# Mobo-v09.net
KiCad netlist of a schematic drawn in EAGLE
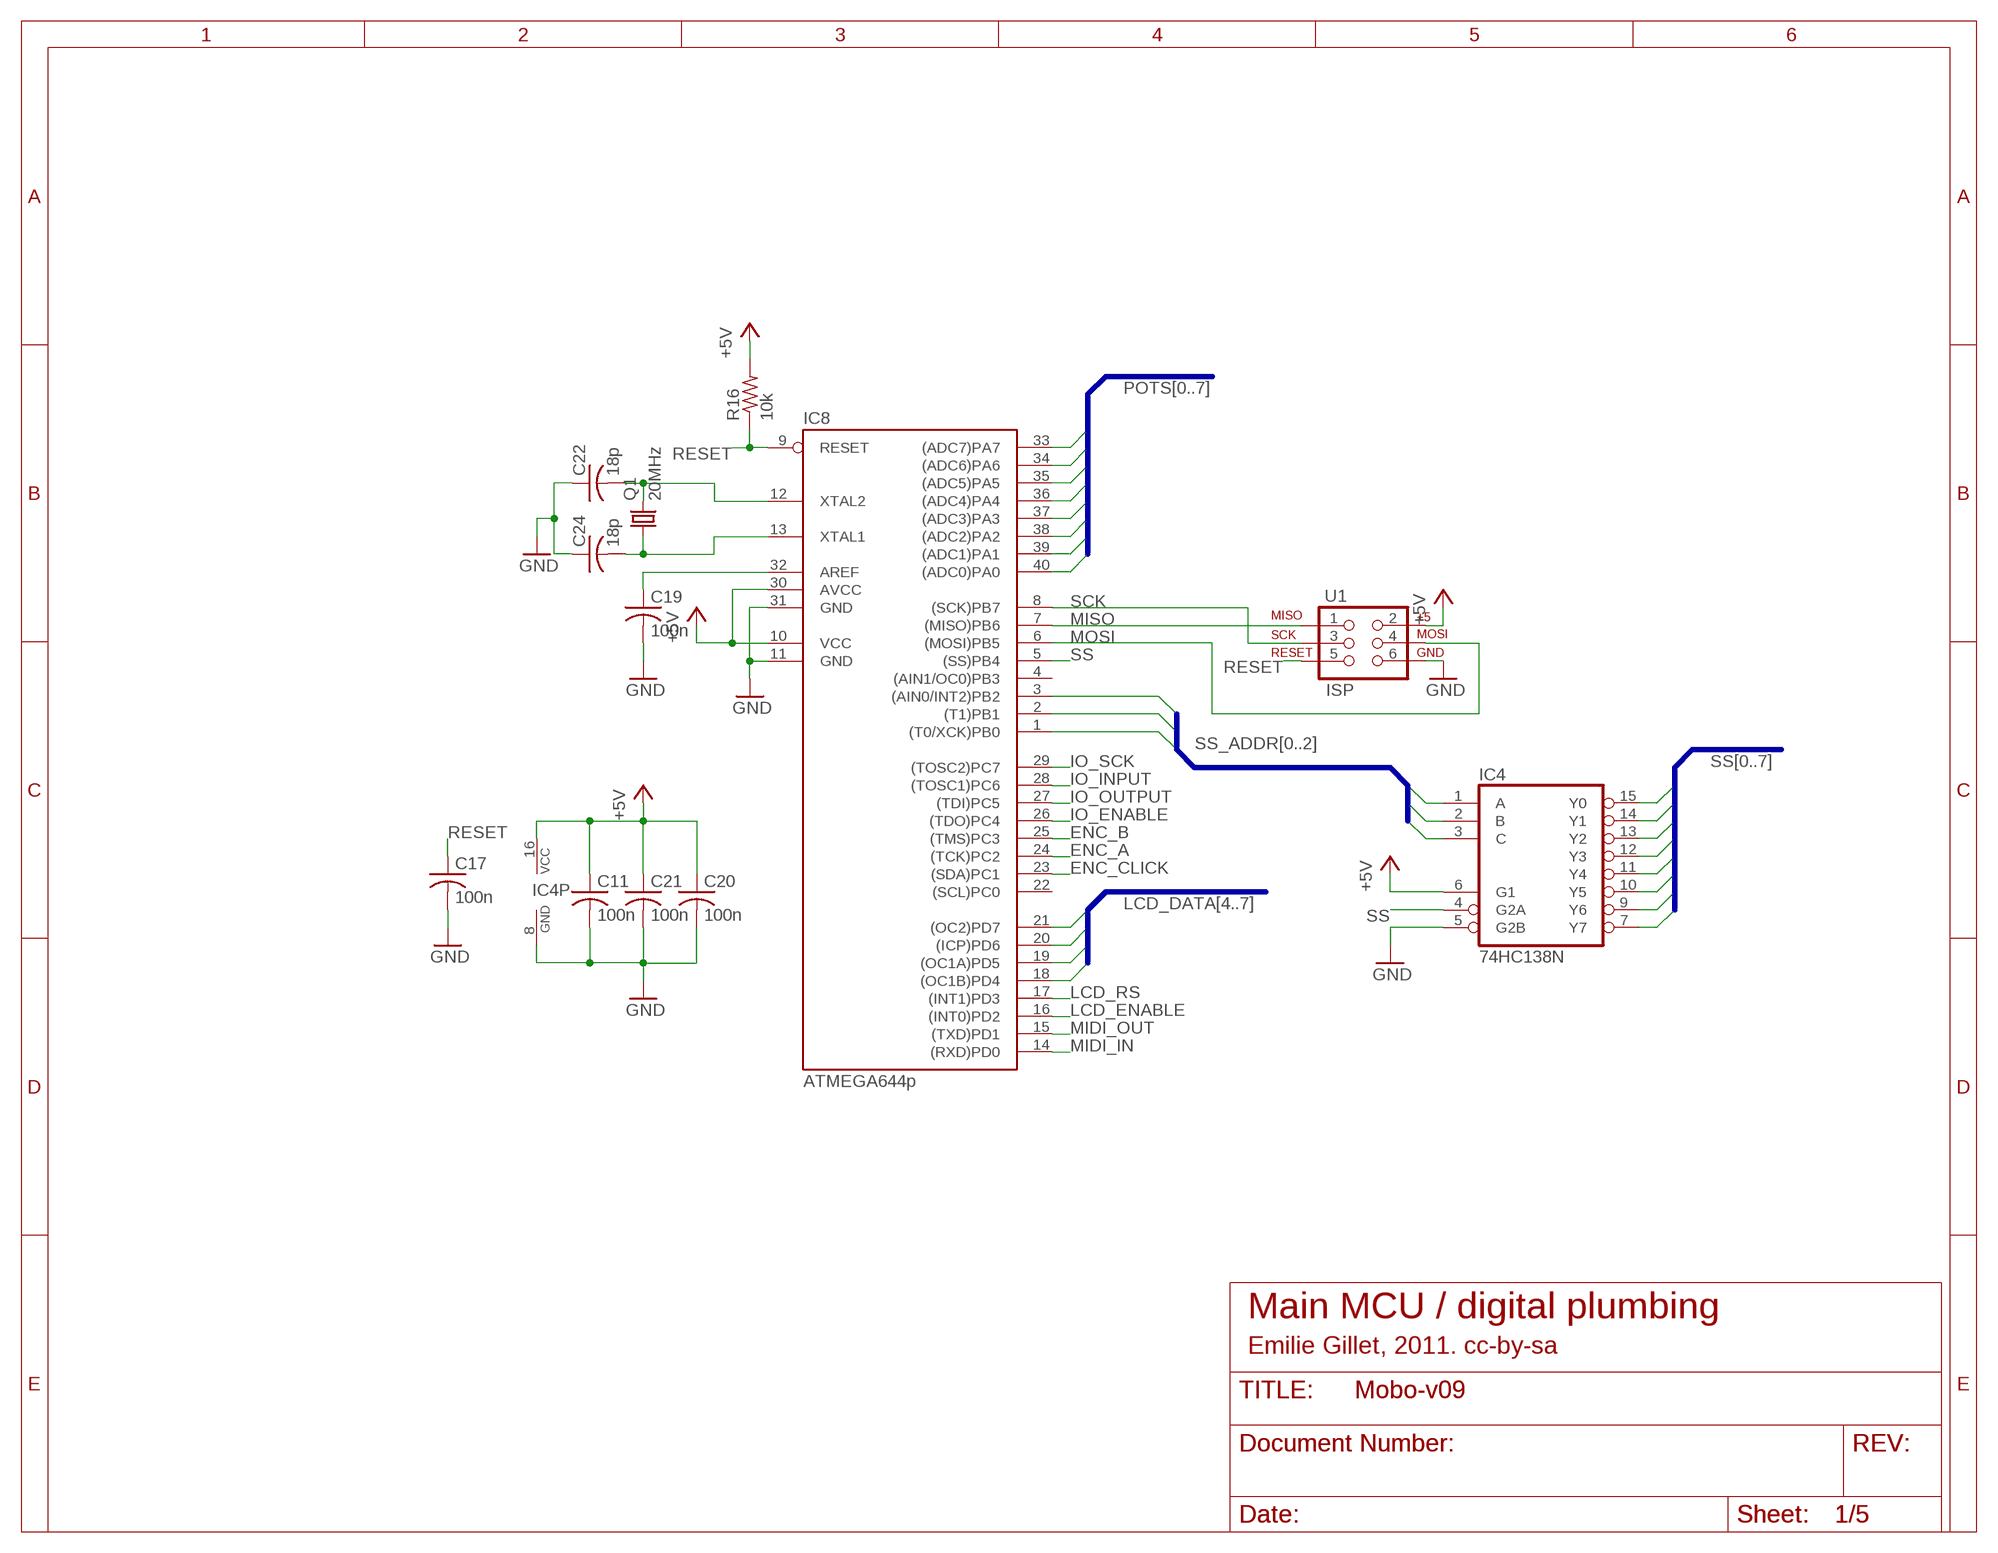
[diagram p0: schematic, sheet 1]
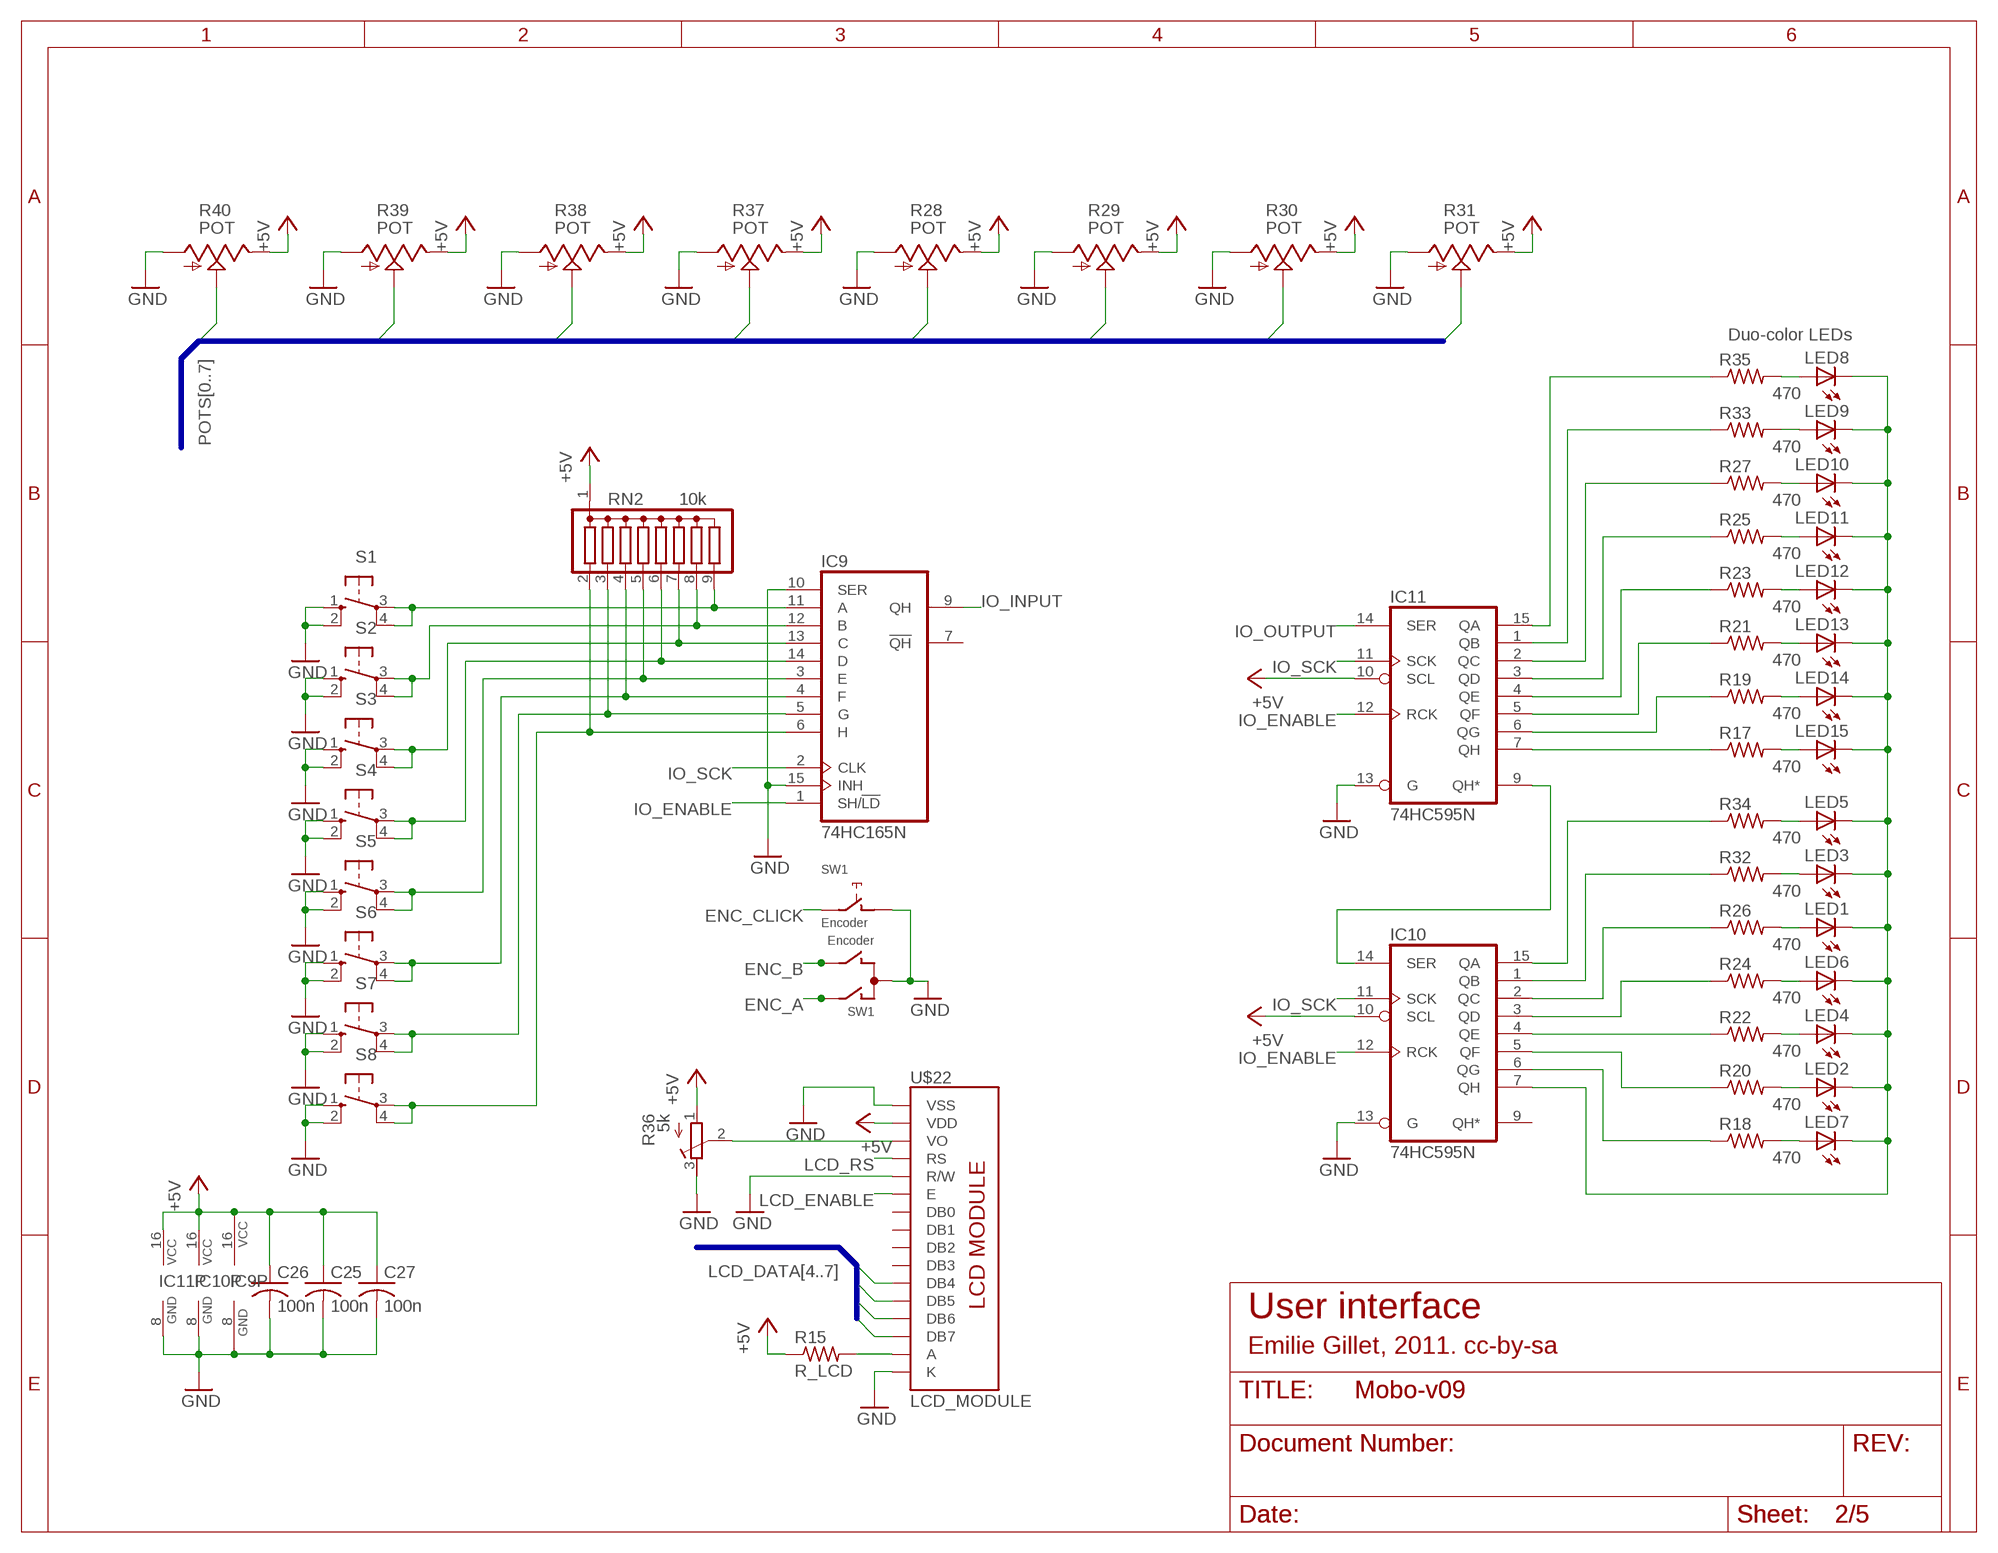
[diagram p1: schematic, sheet 2]
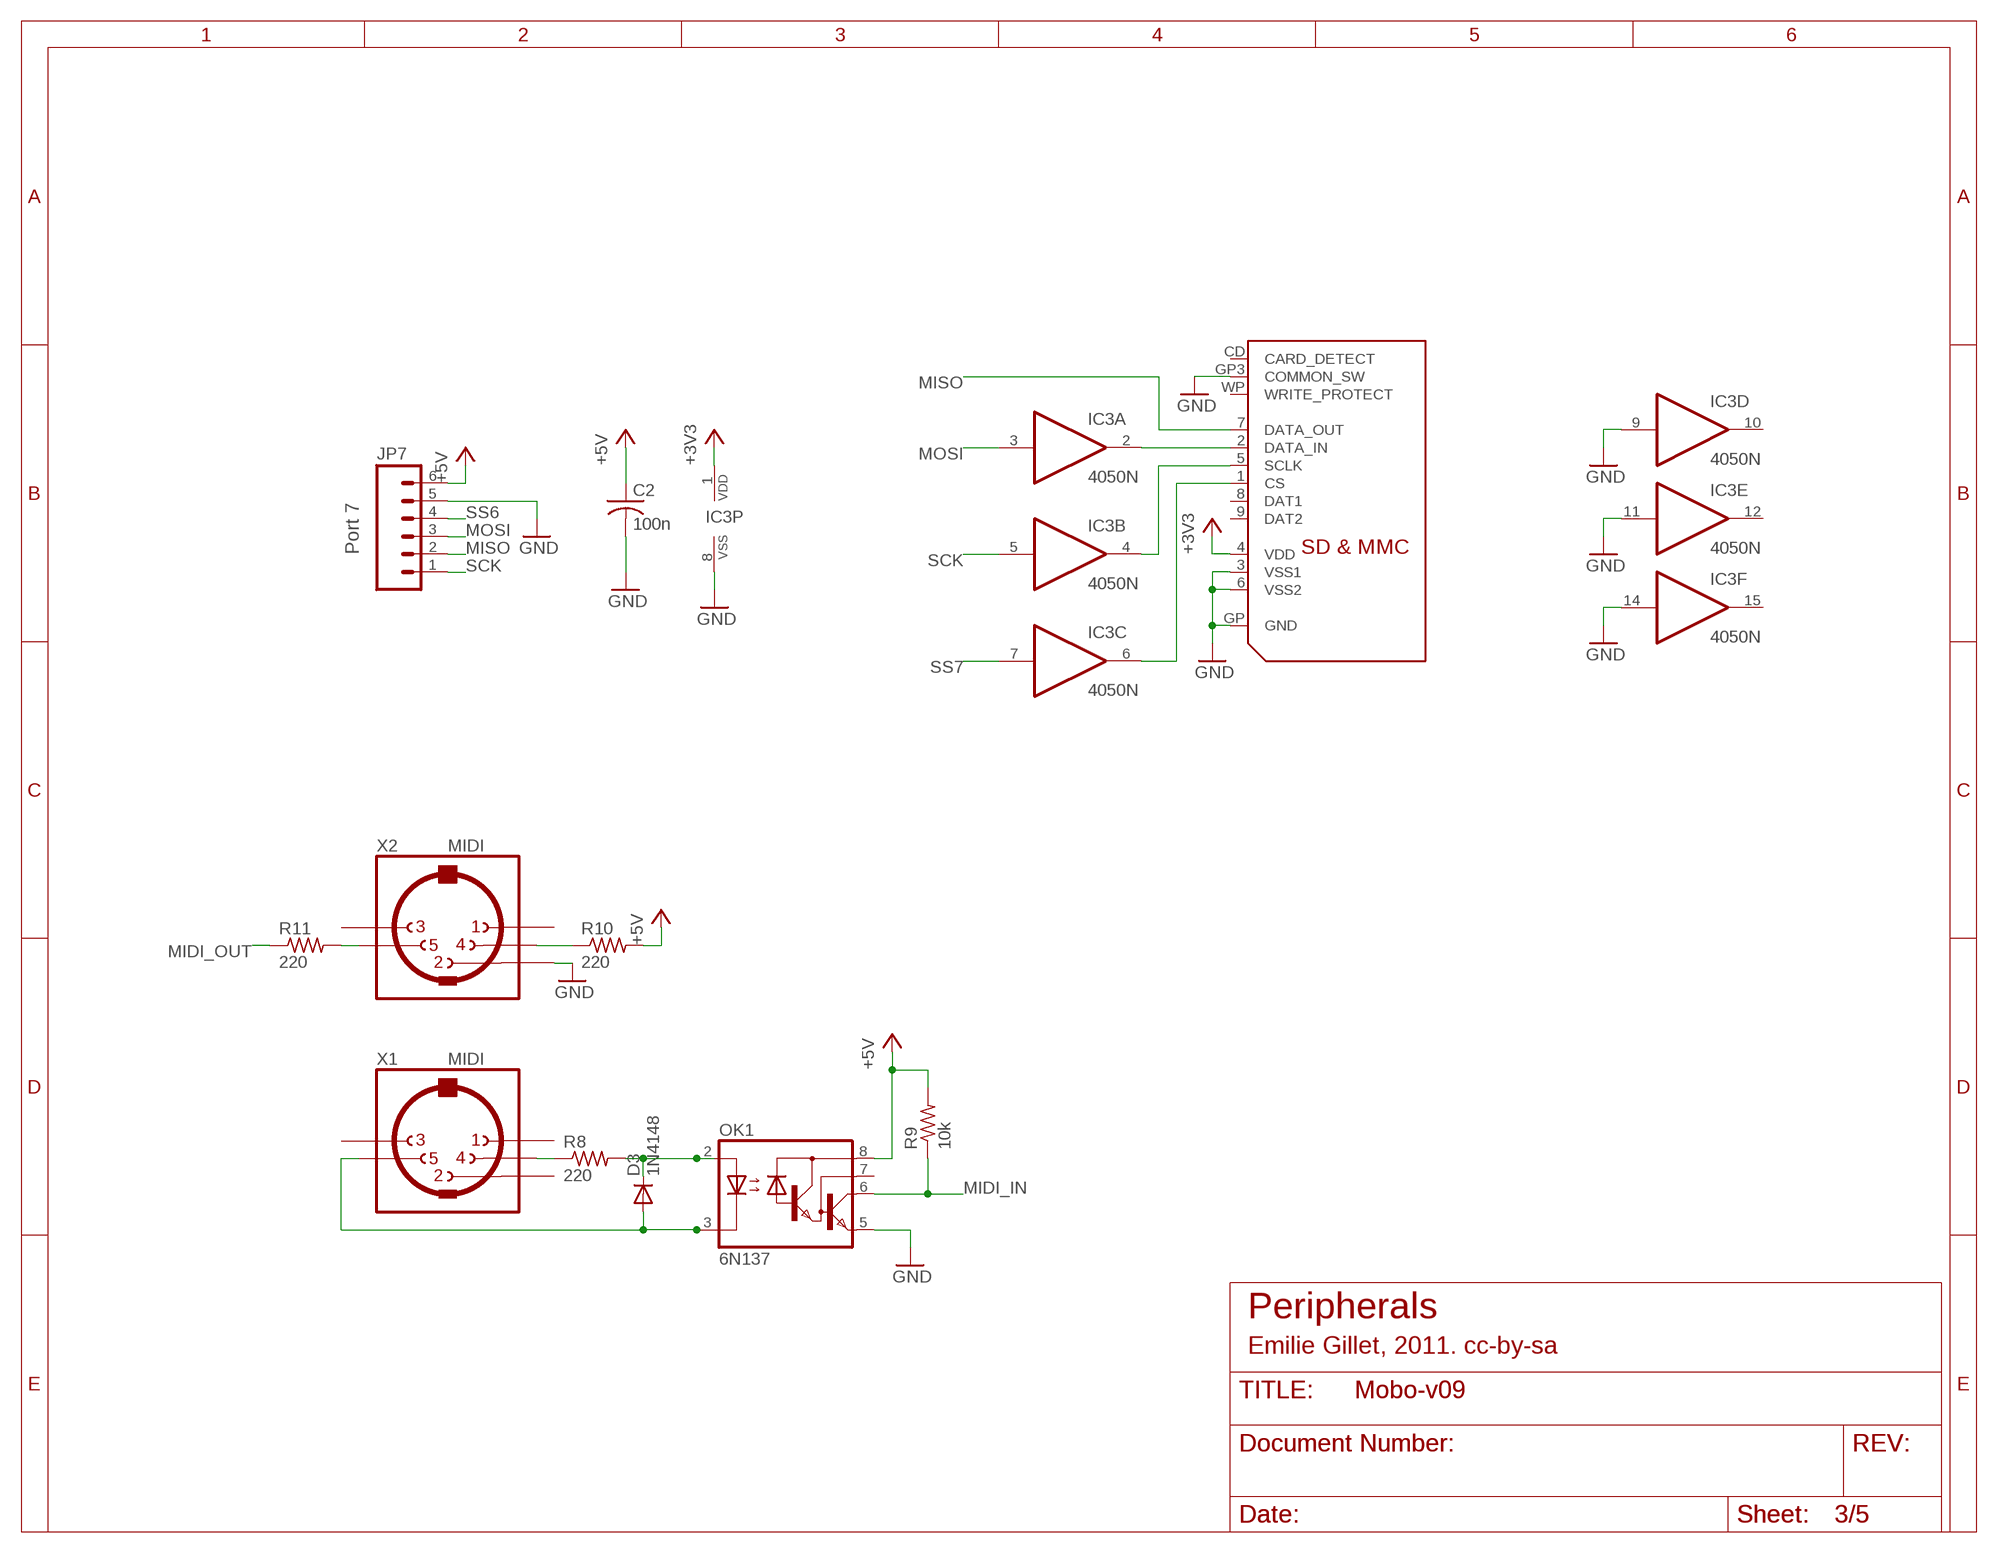
[diagram p2: schematic, sheet 3]
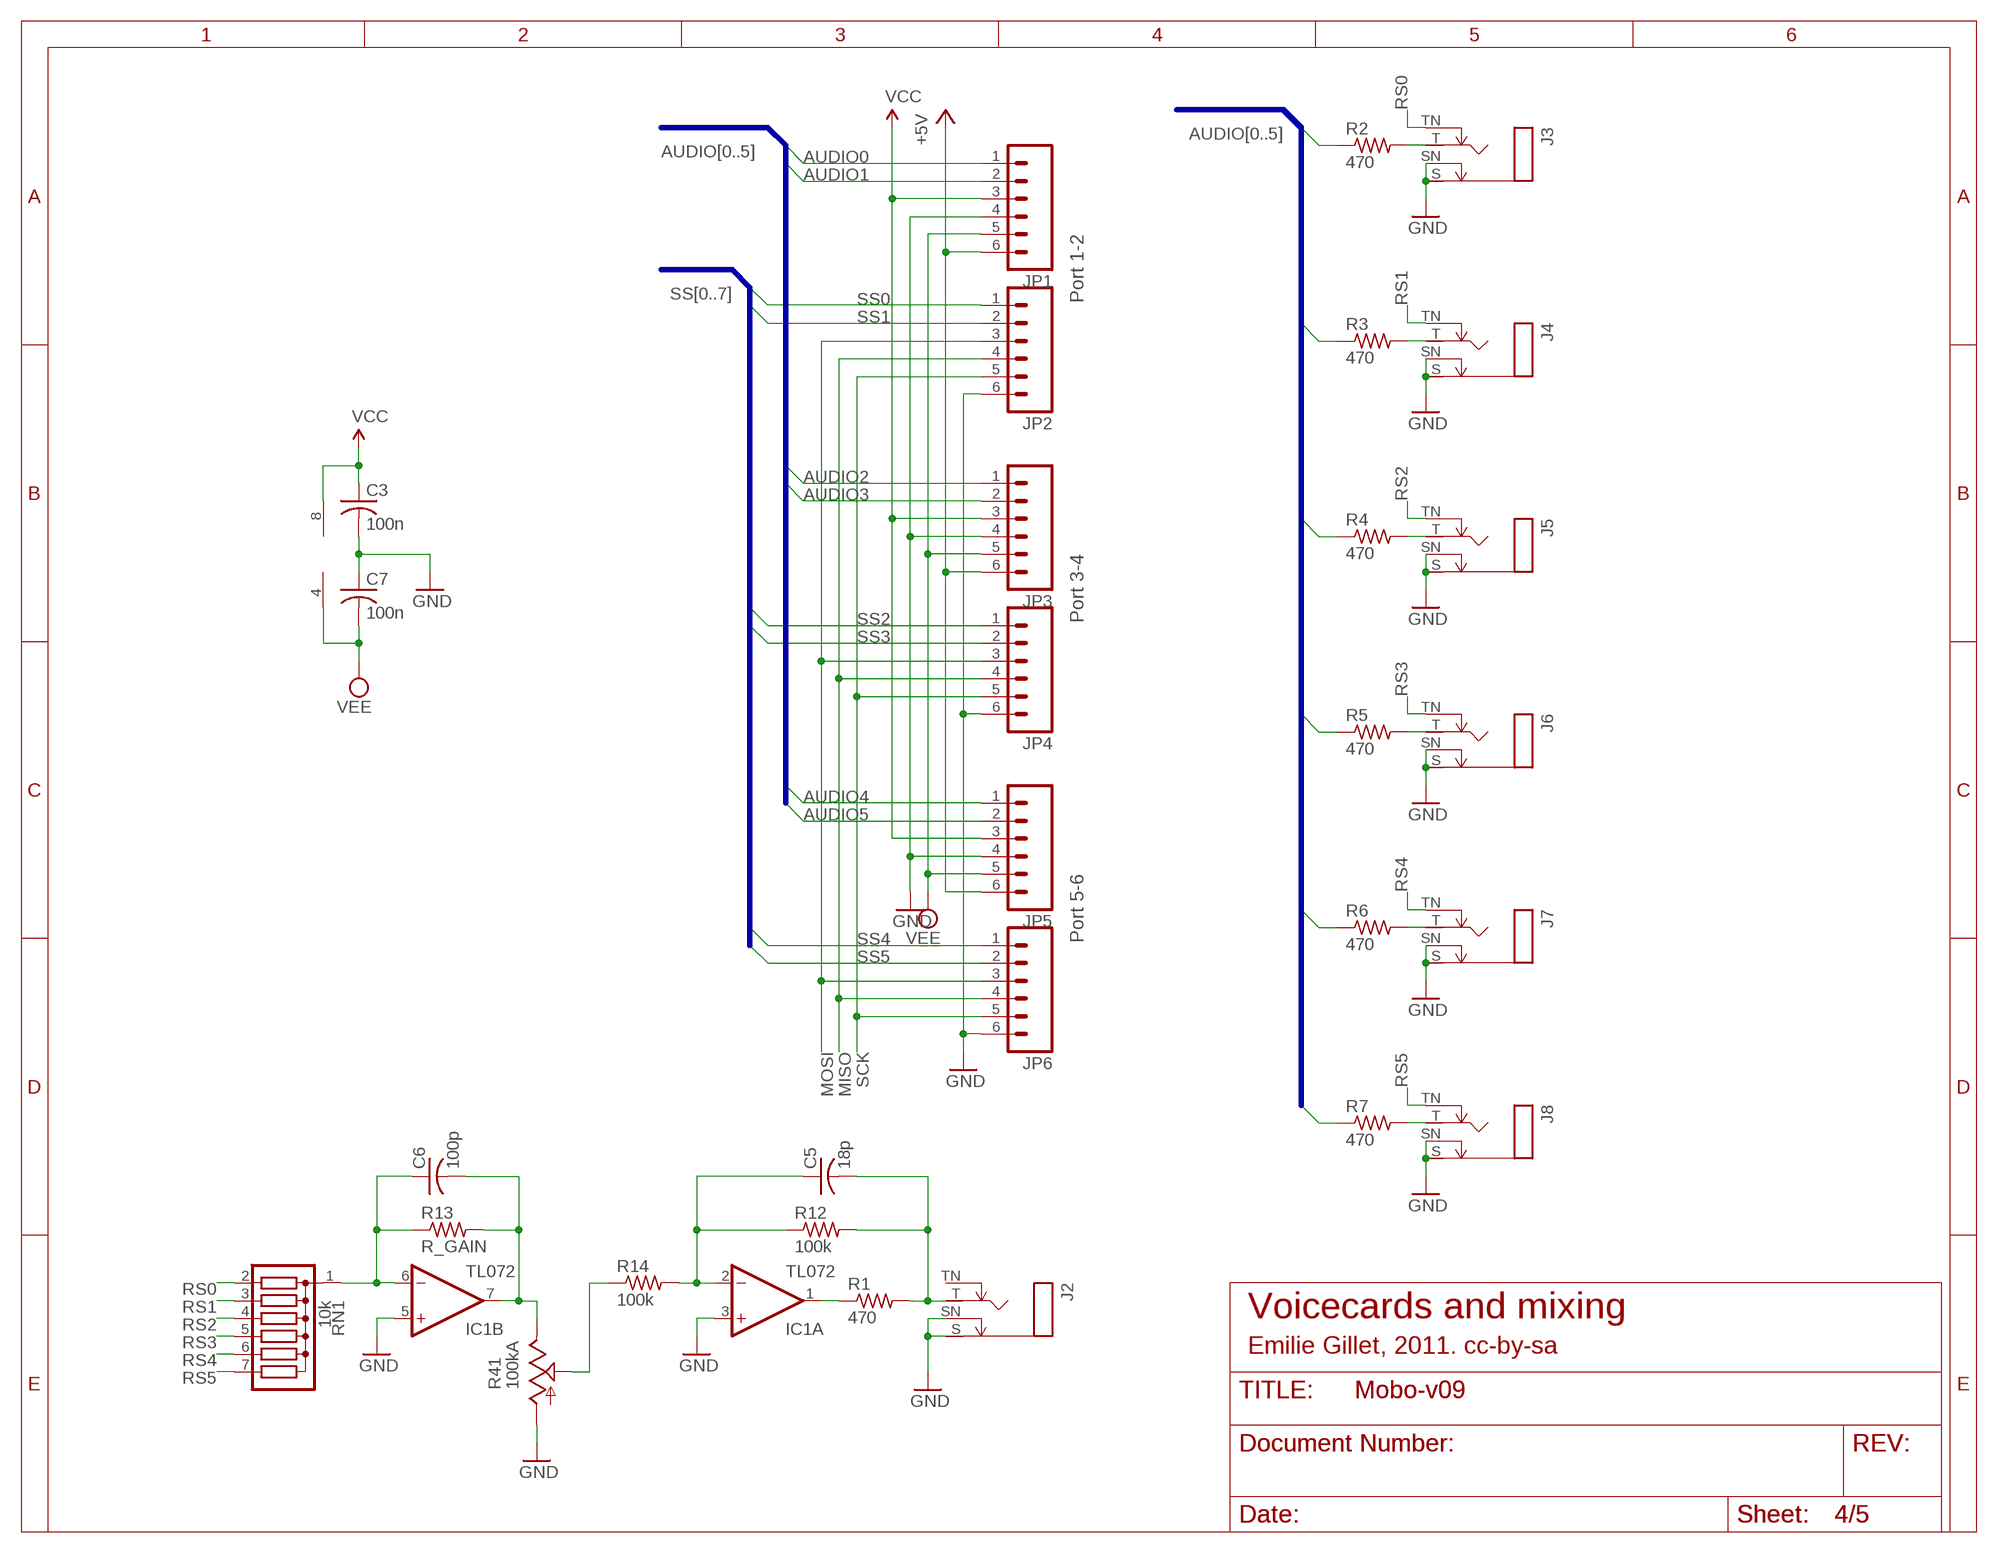
[diagram p3: schematic, sheet 4]
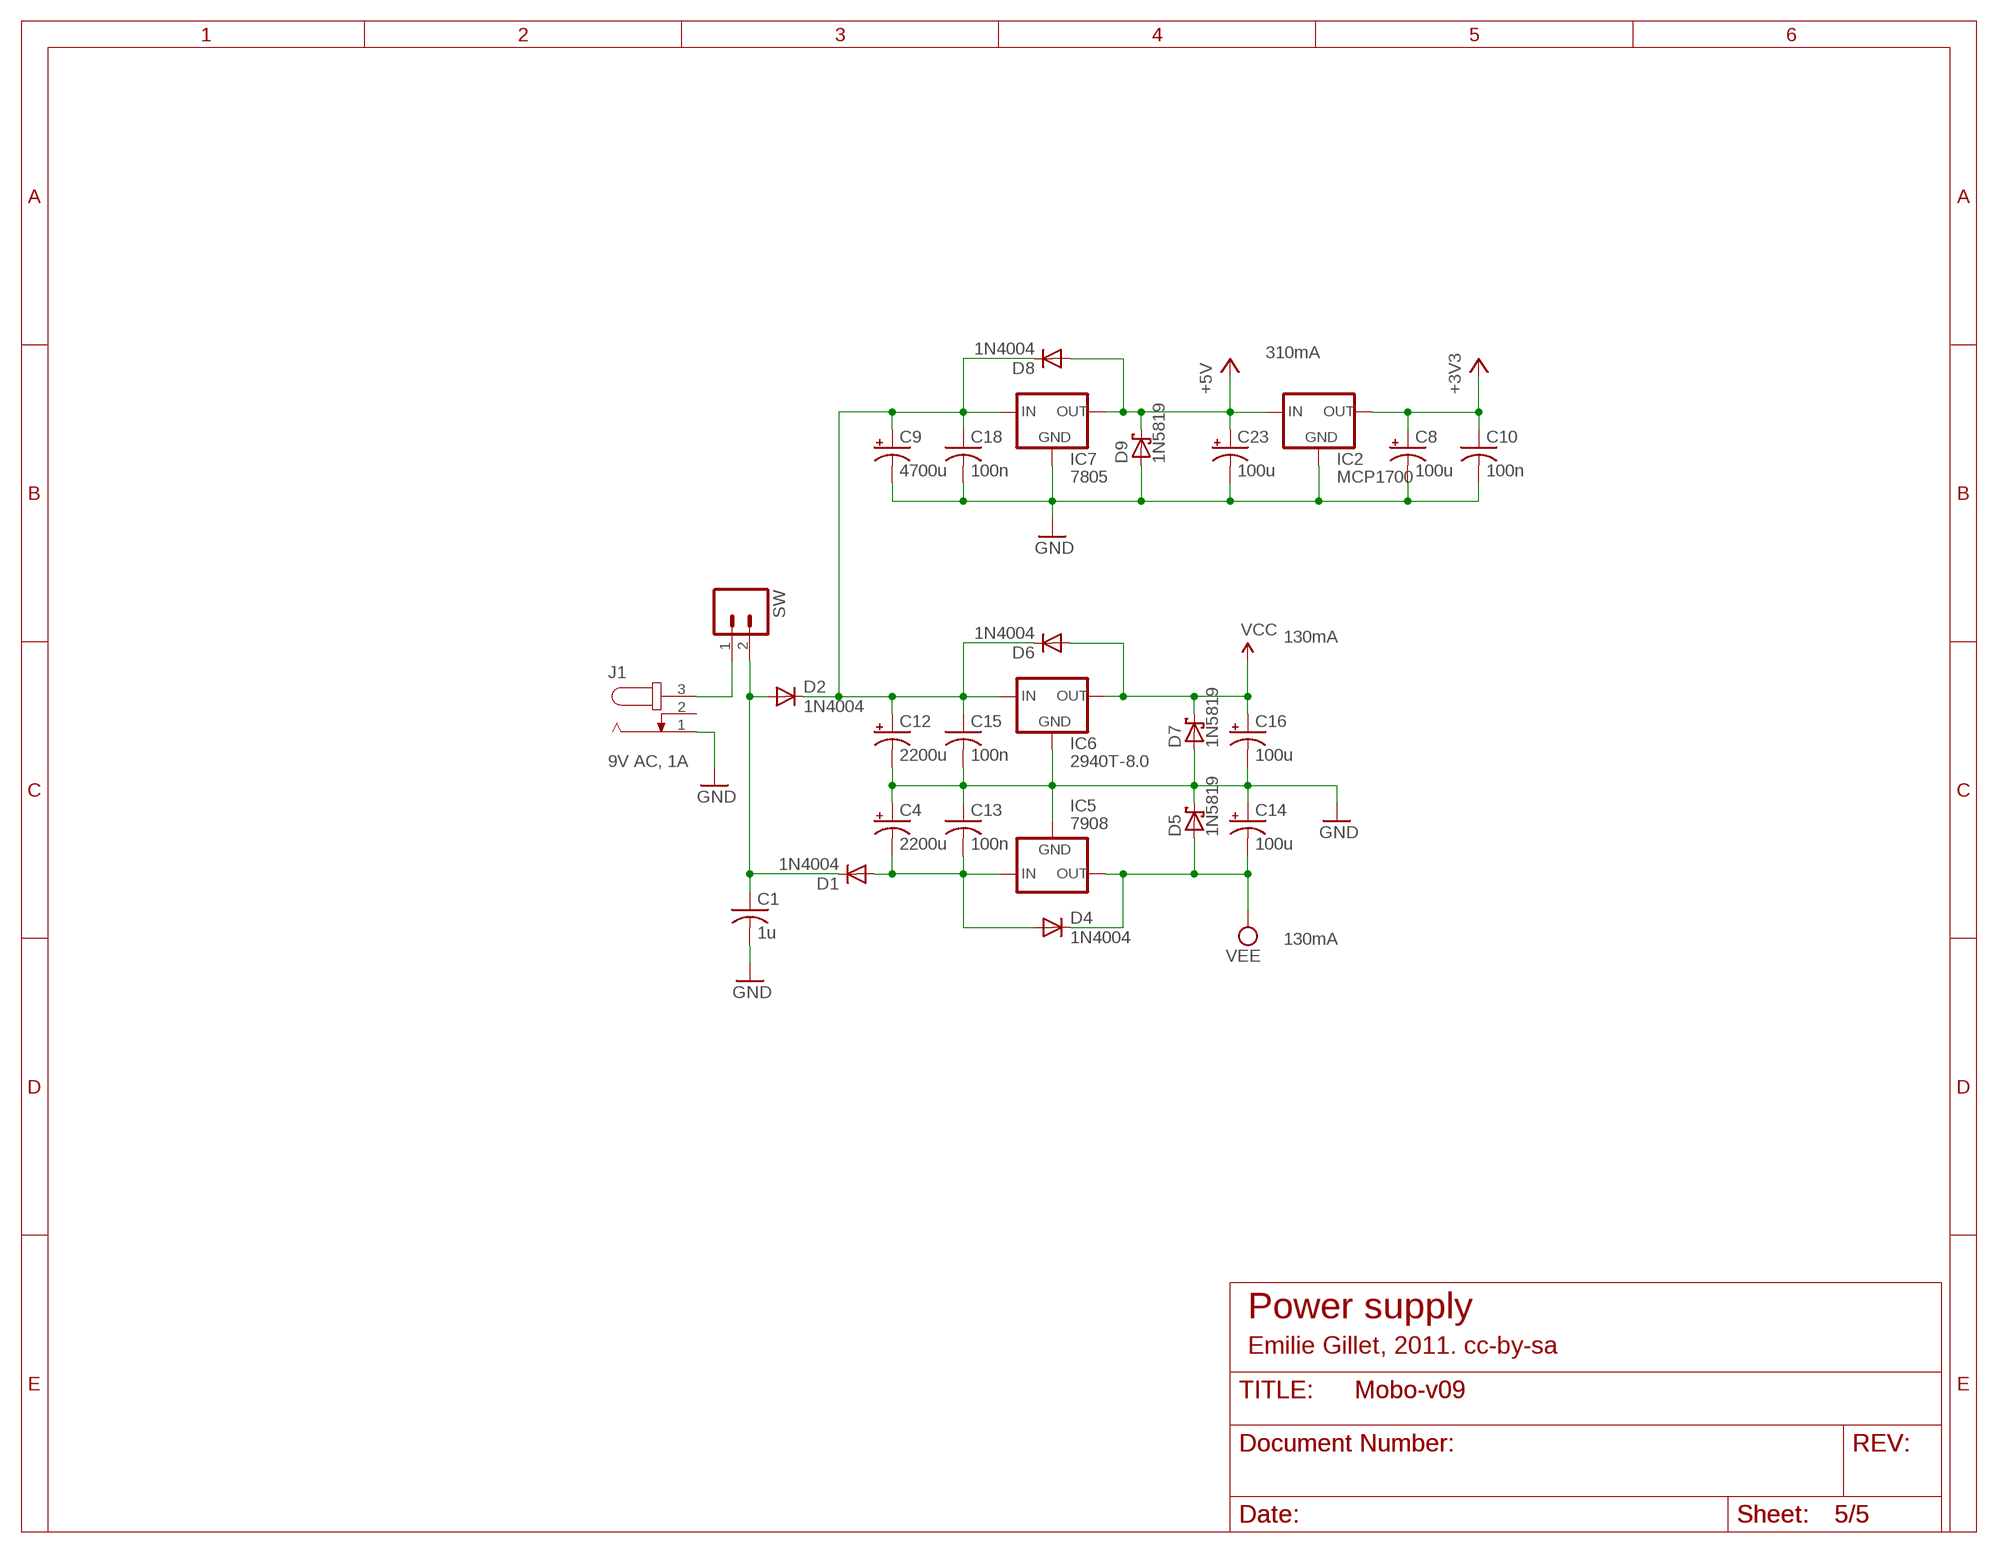
[diagram p4: schematic, sheet 5]

(export (version "E")
  (design (tool "Eeschema 10.0.6"))
  (components
    (comp (ref "C2")
      (value "100n")
      (footprint "eagle-import:C025-024X044")
      (libsource (lib "eagle-import") (part "C-US025-024X044"))
    )
    (comp (ref "D3")
      (value "1N4148")
      (footprint "eagle-import:D-5")
      (libsource (lib "eagle-import") (part "DIODE-D-5"))
    )
    (comp (ref "IC3")
      (value "4050N")
      (footprint "eagle-import:DIL16")
      (libsource (lib "eagle-import") (part "4050N"))
    )
    (comp (ref "JP7")
      (value "M06SIP")
      (footprint "eagle-import:1X06")
      (libsource (lib "eagle-import") (part "M06SIP"))
    )
    (comp (ref "OK1")
      (value "6N137")
      (footprint "eagle-import:DIL08")
      (libsource (lib "eagle-import") (part "6N138"))
    )
    (comp (ref "R8")
      (value "220")
      (footprint "eagle-import:0204_7")
      (libsource (lib "eagle-import") (part "R-US_0204/7"))
    )
    (comp (ref "R9")
      (value "10k")
      (footprint "eagle-import:0204_7")
      (libsource (lib "eagle-import") (part "R-US_0204/7"))
    )
    (comp (ref "R10")
      (value "220")
      (footprint "eagle-import:0204_7")
      (libsource (lib "eagle-import") (part "R-US_0204/7"))
    )
    (comp (ref "R11")
      (value "220")
      (footprint "eagle-import:0204_7")
      (libsource (lib "eagle-import") (part "R-US_0204/7"))
    )
    (comp (ref "U$26")
      (value "SDMMC06132")
      (footprint "eagle-import:06132")
      (libsource (lib "eagle-import") (part "SDMMC06132"))
    )
    (comp (ref "X1")
      (value "MIDI")
      (footprint "eagle-import:MAB5SH")
      (libsource (lib "eagle-import") (part "MAB5SH"))
    )
    (comp (ref "X2")
      (value "MIDI")
      (footprint "eagle-import:MAB5SH")
      (libsource (lib "eagle-import") (part "MAB5SH"))
    )
    (comp (ref "C1")
      (value "1u")
      (footprint "eagle-import:C075-052X106")
      (libsource (lib "eagle-import") (part "C-US075-052X106"))
    )
    (comp (ref "C4")
      (value "2200u")
      (footprint "eagle-import:E5-13")
      (libsource (lib "eagle-import") (part "CPOL-USE5-13"))
    )
    (comp (ref "C8")
      (value "100u")
      (footprint "eagle-import:E2,5-7")
      (libsource (lib "eagle-import") (part "CPOL-USE2.5-7"))
    )
    (comp (ref "C9")
      (value "4700u")
      (footprint "eagle-import:E7,5-16")
      (libsource (lib "eagle-import") (part "CPOL-USE7.5-16"))
    )
    (comp (ref "C10")
      (value "100n")
      (footprint "eagle-import:C025-024X044")
      (libsource (lib "eagle-import") (part "C-US025-024X044"))
    )
    (comp (ref "C12")
      (value "2200u")
      (footprint "eagle-import:E5-13")
      (libsource (lib "eagle-import") (part "CPOL-USE5-13"))
    )
    (comp (ref "C13")
      (value "100n")
      (footprint "eagle-import:C025-025X050")
      (libsource (lib "eagle-import") (part "C-US025-025X050"))
    )
    (comp (ref "C14")
      (value "100u")
      (footprint "eagle-import:E2,5-7")
      (libsource (lib "eagle-import") (part "CPOL-USE2.5-7"))
    )
    (comp (ref "C15")
      (value "100n")
      (footprint "eagle-import:C025-025X050")
      (libsource (lib "eagle-import") (part "C-US025-025X050"))
    )
    (comp (ref "C16")
      (value "100u")
      (footprint "eagle-import:E2,5-7")
      (libsource (lib "eagle-import") (part "CPOL-USE2.5-7"))
    )
    (comp (ref "C18")
      (value "100n")
      (footprint "eagle-import:C025-025X050")
      (libsource (lib "eagle-import") (part "C-US025-025X050"))
    )
    (comp (ref "C23")
      (value "100u")
      (footprint "eagle-import:E2,5-7")
      (libsource (lib "eagle-import") (part "CPOL-USE2.5-7"))
    )
    (comp (ref "D1")
      (value "1N4004")
      (footprint "eagle-import:DO41-10")
      (libsource (lib "eagle-import") (part "1N4004"))
    )
    (comp (ref "D2")
      (value "1N4004")
      (footprint "eagle-import:DO41-10")
      (libsource (lib "eagle-import") (part "1N4004"))
    )
    (comp (ref "D4")
      (value "1N4004")
      (footprint "eagle-import:DO41-10")
      (libsource (lib "eagle-import") (part "1N4004"))
    )
    (comp (ref "D5")
      (value "1N5819")
      (footprint "eagle-import:DO41-7.6")
      (libsource (lib "eagle-import") (part "1N5819-T"))
    )
    (comp (ref "D6")
      (value "1N4004")
      (footprint "eagle-import:DO41-10")
      (libsource (lib "eagle-import") (part "1N4004"))
    )
    (comp (ref "D7")
      (value "1N5819")
      (footprint "eagle-import:DO41-7.6")
      (libsource (lib "eagle-import") (part "1N5819-T"))
    )
    (comp (ref "D8")
      (value "1N4004")
      (footprint "eagle-import:DO41-10")
      (libsource (lib "eagle-import") (part "1N4004"))
    )
    (comp (ref "D9")
      (value "1N5819")
      (footprint "eagle-import:DO41-7.6")
      (libsource (lib "eagle-import") (part "1N5819-T"))
    )
    (comp (ref "IC2")
      (value "MCP1700")
      (footprint "eagle-import:TO92-INLINE")
      (libsource (lib "eagle-import") (part "MCP1700INLINE"))
    )
    (comp (ref "IC5")
      (value "7908")
      (footprint "eagle-import:79XXL")
      (libsource (lib "eagle-import") (part "79XXL"))
    )
    (comp (ref "IC6")
      (value "2940T-8.0")
      (footprint "eagle-import:78XXL")
      (libsource (lib "eagle-import") (part "78XXL"))
    )
    (comp (ref "IC7")
      (value "7805")
      (footprint "eagle-import:78XXL")
      (libsource (lib "eagle-import") (part "v-reg_409_78XXL"))
    )
    (comp (ref "J1")
      (value "JACK-PLUG2")
      (footprint "eagle-import:SPC4078_BIG_HOLES")
      (libsource (lib "eagle-import") (part "JACK-PLUG2"))
    )
    (comp (ref "SW")
      (value "M02PTH")
      (footprint "eagle-import:1X02")
      (libsource (lib "eagle-import") (part "M02PTH"))
    )
    (comp (ref "C3")
      (value "100n")
      (footprint "eagle-import:C025-024X044")
      (libsource (lib "eagle-import") (part "C-US025-024X044"))
    )
    (comp (ref "C5")
      (value "18p")
      (footprint "eagle-import:C025-024X044")
      (libsource (lib "eagle-import") (part "C-US025-024X044"))
    )
    (comp (ref "C6")
      (value "100p")
      (footprint "eagle-import:C025-024X044")
      (libsource (lib "eagle-import") (part "C-US025-024X044"))
    )
    (comp (ref "C7")
      (value "100n")
      (footprint "eagle-import:C025-024X044")
      (libsource (lib "eagle-import") (part "C-US025-024X044"))
    )
    (comp (ref "IC1")
      (value "TL072")
      (footprint "eagle-import:DIL08")
      (libsource (lib "eagle-import") (part "TL072P"))
    )
    (comp (ref "J2")
      (value "MONOSWSLIM")
      (footprint "eagle-import:NRJ4HF")
      (libsource (lib "eagle-import") (part "MONOSWSLIM"))
    )
    (comp (ref "J3")
      (value "MONOSWSLIM")
      (footprint "eagle-import:NRJ4HF")
      (libsource (lib "eagle-import") (part "MONOSWSLIM"))
    )
    (comp (ref "J4")
      (value "MONOSWSLIM")
      (footprint "eagle-import:NRJ4HF")
      (libsource (lib "eagle-import") (part "MONOSWSLIM"))
    )
    (comp (ref "J5")
      (value "MONOSWSLIM")
      (footprint "eagle-import:NRJ4HF")
      (libsource (lib "eagle-import") (part "MONOSWSLIM"))
    )
    (comp (ref "J6")
      (value "MONOSWSLIM")
      (footprint "eagle-import:NRJ4HF")
      (libsource (lib "eagle-import") (part "MONOSWSLIM"))
    )
    (comp (ref "J7")
      (value "MONOSWSLIM")
      (footprint "eagle-import:NRJ4HF")
      (libsource (lib "eagle-import") (part "MONOSWSLIM"))
    )
    (comp (ref "J8")
      (value "MONOSWSLIM")
      (footprint "eagle-import:NRJ4HF")
      (libsource (lib "eagle-import") (part "MONOSWSLIM"))
    )
    (comp (ref "JP1")
      (value "M06SIP")
      (footprint "eagle-import:1X06")
      (libsource (lib "eagle-import") (part "M06SIP"))
    )
    (comp (ref "JP2")
      (value "M06SIP")
      (footprint "eagle-import:1X06")
      (libsource (lib "eagle-import") (part "M06SIP"))
    )
    (comp (ref "JP3")
      (value "M06SIP")
      (footprint "eagle-import:1X06")
      (libsource (lib "eagle-import") (part "M06SIP"))
    )
    (comp (ref "JP4")
      (value "M06SIP")
      (footprint "eagle-import:1X06")
      (libsource (lib "eagle-import") (part "M06SIP"))
    )
    (comp (ref "JP5")
      (value "M06SIP")
      (footprint "eagle-import:1X06")
      (libsource (lib "eagle-import") (part "M06SIP"))
    )
    (comp (ref "JP6")
      (value "M06SIP")
      (footprint "eagle-import:1X06")
      (libsource (lib "eagle-import") (part "M06SIP"))
    )
    (comp (ref "R1")
      (value "470")
      (footprint "eagle-import:0204_7")
      (libsource (lib "eagle-import") (part "R-US_0204/7"))
    )
    (comp (ref "R2")
      (value "470")
      (footprint "eagle-import:0204_7")
      (libsource (lib "eagle-import") (part "R-US_0204/7"))
    )
    (comp (ref "R3")
      (value "470")
      (footprint "eagle-import:0204_7")
      (libsource (lib "eagle-import") (part "R-US_0204/7"))
    )
    (comp (ref "R4")
      (value "470")
      (footprint "eagle-import:0204_7")
      (libsource (lib "eagle-import") (part "R-US_0204/7"))
    )
    (comp (ref "R5")
      (value "470")
      (footprint "eagle-import:0204_7")
      (libsource (lib "eagle-import") (part "R-US_0204/7"))
    )
    (comp (ref "R6")
      (value "470")
      (footprint "eagle-import:0204_7")
      (libsource (lib "eagle-import") (part "R-US_0204/7"))
    )
    (comp (ref "R7")
      (value "470")
      (footprint "eagle-import:0204_7")
      (libsource (lib "eagle-import") (part "R-US_0204/7"))
    )
    (comp (ref "R12")
      (value "100k")
      (footprint "eagle-import:0204_7")
      (libsource (lib "eagle-import") (part "R-US_0204/7"))
    )
    (comp (ref "R13")
      (value "R_GAIN")
      (footprint "eagle-import:0204_7")
      (libsource (lib "eagle-import") (part "R-US_0204/7"))
    )
    (comp (ref "R14")
      (value "100k")
      (footprint "eagle-import:0204_7")
      (libsource (lib "eagle-import") (part "R-US_0204/7"))
    )
    (comp (ref "R41")
      (value "100kA")
      (footprint "eagle-import:ALPS_POT_VERTICAL")
      (libsource (lib "eagle-import") (part "POT_USVERTICAL"))
    )
    (comp (ref "RN1")
      (value "10k")
      (footprint "eagle-import:SIL7")
      (libsource (lib "eagle-import") (part "G06R"))
    )
    (comp (ref "C11")
      (value "100n")
      (footprint "eagle-import:C025-024X044")
      (libsource (lib "eagle-import") (part "C-US025-024X044"))
    )
    (comp (ref "C17")
      (value "100n")
      (footprint "eagle-import:C025-024X044")
      (libsource (lib "eagle-import") (part "C-US025-024X044"))
    )
    (comp (ref "C19")
      (value "100n")
      (footprint "eagle-import:C025-024X044")
      (libsource (lib "eagle-import") (part "C-US025-024X044"))
    )
    (comp (ref "C20")
      (value "100n")
      (footprint "eagle-import:C025-024X044")
      (libsource (lib "eagle-import") (part "C-US025-024X044"))
    )
    (comp (ref "C21")
      (value "100n")
      (footprint "eagle-import:C025-024X044")
      (libsource (lib "eagle-import") (part "C-US025-024X044"))
    )
    (comp (ref "C22")
      (value "18p")
      (footprint "eagle-import:C025-024X044")
      (libsource (lib "eagle-import") (part "C-US025-024X044"))
    )
    (comp (ref "C24")
      (value "18p")
      (footprint "eagle-import:C025-024X044")
      (libsource (lib "eagle-import") (part "C-US025-024X044"))
    )
    (comp (ref "IC4")
      (value "74HC138N")
      (footprint "eagle-import:DIL16")
      (libsource (lib "eagle-import") (part "74138NHC"))
    )
    (comp (ref "IC8")
      (value "ATMEGA644p")
      (footprint "eagle-import:DIL40")
      (libsource (lib "eagle-import") (part "MEGA16-P"))
    )
    (comp (ref "Q1")
      (value "20MHz")
      (footprint "eagle-import:HC49U-V")
      (libsource (lib "eagle-import") (part "CRYSTALHC49U-V"))
    )
    (comp (ref "R16")
      (value "10k")
      (footprint "eagle-import:0204_7")
      (libsource (lib "eagle-import") (part "R-US_0204/7"))
    )
    (comp (ref "U1")
      (value "ISP")
      (footprint "eagle-import:2X3")
      (libsource (lib "eagle-import") (part "AVR_SPI_PRG_6PTH"))
    )
    (comp (ref "C25")
      (value "100n")
      (footprint "eagle-import:C025-024X044")
      (libsource (lib "eagle-import") (part "C-US025-024X044"))
    )
    (comp (ref "C26")
      (value "100n")
      (footprint "eagle-import:C025-024X044")
      (libsource (lib "eagle-import") (part "C-US025-024X044"))
    )
    (comp (ref "C27")
      (value "100n")
      (footprint "eagle-import:C025-024X044")
      (libsource (lib "eagle-import") (part "C-US025-024X044"))
    )
    (comp (ref "IC9")
      (value "74HC165N")
      (footprint "eagle-import:DIL16")
      (libsource (lib "eagle-import") (part "74165NLS"))
    )
    (comp (ref "IC10")
      (value "74HC595N")
      (footprint "eagle-import:DIL16")
      (libsource (lib "eagle-import") (part "74595NHC"))
    )
    (comp (ref "IC11")
      (value "74HC595N")
      (footprint "eagle-import:DIL16")
      (libsource (lib "eagle-import") (part "74595NHC"))
    )
    (comp (ref "LED1")
      (value "LED3MM")
      (footprint "eagle-import:LED3MM")
      (libsource (lib "eagle-import") (part "LED3MM"))
    )
    (comp (ref "LED2")
      (value "LED3MM")
      (footprint "eagle-import:LED3MM")
      (libsource (lib "eagle-import") (part "LED3MM"))
    )
    (comp (ref "LED3")
      (value "LED3MM")
      (footprint "eagle-import:LED3MM")
      (libsource (lib "eagle-import") (part "LED3MM"))
    )
    (comp (ref "LED4")
      (value "LED3MM")
      (footprint "eagle-import:LED3MM")
      (libsource (lib "eagle-import") (part "LED3MM"))
    )
    (comp (ref "LED5")
      (value "LED3MM")
      (footprint "eagle-import:LED3MM")
      (libsource (lib "eagle-import") (part "LED3MM"))
    )
    (comp (ref "LED6")
      (value "LED3MM")
      (footprint "eagle-import:LED3MM")
      (libsource (lib "eagle-import") (part "LED3MM"))
    )
    (comp (ref "LED7")
      (value "LED3MM")
      (footprint "eagle-import:LED3MM")
      (libsource (lib "eagle-import") (part "LED3MM"))
    )
    (comp (ref "LED8")
      (value "LED3MM")
      (footprint "eagle-import:LED3MM")
      (libsource (lib "eagle-import") (part "LED3MM"))
    )
    (comp (ref "LED9")
      (value "LED3MM")
      (footprint "eagle-import:LED3MM")
      (libsource (lib "eagle-import") (part "LED3MM"))
    )
    (comp (ref "LED10")
      (value "LED3MM")
      (footprint "eagle-import:LED3MM")
      (libsource (lib "eagle-import") (part "LED3MM"))
    )
    (comp (ref "LED11")
      (value "LED3MM")
      (footprint "eagle-import:LED3MM")
      (libsource (lib "eagle-import") (part "LED3MM"))
    )
    (comp (ref "LED12")
      (value "LED3MM")
      (footprint "eagle-import:LED3MM")
      (libsource (lib "eagle-import") (part "LED3MM"))
    )
    (comp (ref "LED13")
      (value "LED3MM")
      (footprint "eagle-import:LED3MM")
      (libsource (lib "eagle-import") (part "LED3MM"))
    )
    (comp (ref "LED14")
      (value "LED3MM")
      (footprint "eagle-import:LED3MM")
      (libsource (lib "eagle-import") (part "LED3MM"))
    )
    (comp (ref "LED15")
      (value "LED3MM")
      (footprint "eagle-import:LED3MM")
      (libsource (lib "eagle-import") (part "LED3MM"))
    )
    (comp (ref "R15")
      (value "R_LCD")
      (footprint "eagle-import:0204_7")
      (libsource (lib "eagle-import") (part "R-US_0204/7"))
    )
    (comp (ref "R17")
      (value "470")
      (footprint "eagle-import:0204_7")
      (libsource (lib "eagle-import") (part "R-US_0204/7"))
    )
    (comp (ref "R18")
      (value "470")
      (footprint "eagle-import:0204_7")
      (libsource (lib "eagle-import") (part "R-US_0204/7"))
    )
    (comp (ref "R19")
      (value "470")
      (footprint "eagle-import:0204_7")
      (libsource (lib "eagle-import") (part "R-US_0204/7"))
    )
    (comp (ref "R20")
      (value "470")
      (footprint "eagle-import:0204_7")
      (libsource (lib "eagle-import") (part "R-US_0204/7"))
    )
    (comp (ref "R21")
      (value "470")
      (footprint "eagle-import:0204_7")
      (libsource (lib "eagle-import") (part "R-US_0204/7"))
    )
    (comp (ref "R22")
      (value "470")
      (footprint "eagle-import:0204_7")
      (libsource (lib "eagle-import") (part "R-US_0204/7"))
    )
    (comp (ref "R23")
      (value "470")
      (footprint "eagle-import:0204_7")
      (libsource (lib "eagle-import") (part "R-US_0204/7"))
    )
    (comp (ref "R24")
      (value "470")
      (footprint "eagle-import:0204_7")
      (libsource (lib "eagle-import") (part "R-US_0204/7"))
    )
    (comp (ref "R25")
      (value "470")
      (footprint "eagle-import:0204_7")
      (libsource (lib "eagle-import") (part "R-US_0204/7"))
    )
    (comp (ref "R26")
      (value "470")
      (footprint "eagle-import:0204_7")
      (libsource (lib "eagle-import") (part "R-US_0204/7"))
    )
    (comp (ref "R27")
      (value "470")
      (footprint "eagle-import:0204_7")
      (libsource (lib "eagle-import") (part "R-US_0204/7"))
    )
    (comp (ref "R28")
      (value "POT")
      (footprint "eagle-import:ALPS_POT_VERTICAL")
      (libsource (lib "eagle-import") (part "POT_USVERTICAL"))
    )
    (comp (ref "R29")
      (value "POT")
      (footprint "eagle-import:ALPS_POT_VERTICAL")
      (libsource (lib "eagle-import") (part "POT_USVERTICAL"))
    )
    (comp (ref "R30")
      (value "POT")
      (footprint "eagle-import:ALPS_POT_VERTICAL")
      (libsource (lib "eagle-import") (part "POT_USVERTICAL"))
    )
    (comp (ref "R31")
      (value "POT")
      (footprint "eagle-import:ALPS_POT_VERTICAL")
      (libsource (lib "eagle-import") (part "POT_USVERTICAL"))
    )
    (comp (ref "R32")
      (value "470")
      (footprint "eagle-import:0204_7")
      (libsource (lib "eagle-import") (part "R-US_0204/7"))
    )
    (comp (ref "R33")
      (value "470")
      (footprint "eagle-import:0204_7")
      (libsource (lib "eagle-import") (part "R-US_0204/7"))
    )
    (comp (ref "R34")
      (value "470")
      (footprint "eagle-import:0204_7")
      (libsource (lib "eagle-import") (part "R-US_0204/7"))
    )
    (comp (ref "R35")
      (value "470")
      (footprint "eagle-import:0204_7")
      (libsource (lib "eagle-import") (part "R-US_0204/7"))
    )
    (comp (ref "R36")
      (value "5k")
      (footprint "eagle-import:RTRIM3339P")
      (libsource (lib "eagle-import") (part "R-TRIMM3339P"))
    )
    (comp (ref "R37")
      (value "POT")
      (footprint "eagle-import:ALPS_POT_VERTICAL")
      (libsource (lib "eagle-import") (part "POT_USVERTICAL"))
    )
    (comp (ref "R38")
      (value "POT")
      (footprint "eagle-import:ALPS_POT_VERTICAL")
      (libsource (lib "eagle-import") (part "POT_USVERTICAL"))
    )
    (comp (ref "R39")
      (value "POT")
      (footprint "eagle-import:ALPS_POT_VERTICAL")
      (libsource (lib "eagle-import") (part "POT_USVERTICAL"))
    )
    (comp (ref "R40")
      (value "POT")
      (footprint "eagle-import:ALPS_POT_VERTICAL")
      (libsource (lib "eagle-import") (part "POT_USVERTICAL"))
    )
    (comp (ref "RN2")
      (value "10k")
      (footprint "eagle-import:SIL9")
      (libsource (lib "eagle-import") (part "G08R"))
    )
    (comp (ref "S1")
      (value "40-XX")
      (footprint "eagle-import:B3F-40XX")
      (libsource (lib "eagle-import") (part "40-XX"))
    )
    (comp (ref "S2")
      (value "40-XX")
      (footprint "eagle-import:B3F-40XX")
      (libsource (lib "eagle-import") (part "40-XX"))
    )
    (comp (ref "S3")
      (value "40-XX")
      (footprint "eagle-import:B3F-40XX")
      (libsource (lib "eagle-import") (part "40-XX"))
    )
    (comp (ref "S4")
      (value "40-XX")
      (footprint "eagle-import:B3F-40XX")
      (libsource (lib "eagle-import") (part "40-XX"))
    )
    (comp (ref "S5")
      (value "40-XX")
      (footprint "eagle-import:B3F-40XX")
      (libsource (lib "eagle-import") (part "40-XX"))
    )
    (comp (ref "S6")
      (value "40-XX")
      (footprint "eagle-import:B3F-40XX")
      (libsource (lib "eagle-import") (part "40-XX"))
    )
    (comp (ref "S7")
      (value "40-XX")
      (footprint "eagle-import:B3F-40XX")
      (libsource (lib "eagle-import") (part "40-XX"))
    )
    (comp (ref "S8")
      (value "40-XX")
      (footprint "eagle-import:B3F-40XX")
      (libsource (lib "eagle-import") (part "40-XX"))
    )
    (comp (ref "SW1")
      (value "Encoder")
      (footprint "eagle-import:ALPS_EC12E_SW")
      (libsource (lib "eagle-import") (part "EC12E_SW"))
    )
    (comp (ref "U$22")
      (value "LCD_MODULE")
      (footprint "eagle-import:LCD_MODULE_2X40")
      (libsource (lib "eagle-import") (part "LCD_MODULE"))
    )
  )
  (nets
    (net (code "3") (name "+3V3") (class "Default")
      (node (ref "C10") (pin "1") (pinfunction "1_1") (pintype "passive"))
      (node (ref "C8") (pin "+") (pinfunction "+_+") (pintype "passive"))
      (node (ref "IC2") (pin "3") (pinfunction "OUT_3") (pintype "passive"))
      (node (ref "IC3") (pin "1") (pinfunction "VDD_1") (pintype "power_in"))
      (node (ref "U$26") (pin "4") (pinfunction "VDD_4") (pintype "power_in"))
    )
    (net (code "4") (name "+5V") (class "Default")
      (node (ref "C11") (pin "1") (pinfunction "1_1") (pintype "passive"))
      (node (ref "C2") (pin "1") (pinfunction "1_1") (pintype "passive"))
      (node (ref "C20") (pin "1") (pinfunction "1_1") (pintype "passive"))
      (node (ref "C21") (pin "1") (pinfunction "1_1") (pintype "passive"))
      (node (ref "C23") (pin "+") (pinfunction "+_+") (pintype "passive"))
      (node (ref "C25") (pin "1") (pinfunction "1_1") (pintype "passive"))
      (node (ref "C26") (pin "1") (pinfunction "1_1") (pintype "passive"))
      (node (ref "C27") (pin "1") (pinfunction "1_1") (pintype "passive"))
      (node (ref "D8") (pin "A") (pinfunction "A_A") (pintype "passive"))
      (node (ref "D9") (pin "C") (pinfunction "C_C") (pintype "passive"))
      (node (ref "IC10") (pin "10") (pinfunction "SCL_10") (pintype "input"))
      (node (ref "IC10") (pin "16") (pinfunction "VCC_16") (pintype "power_in"))
      (node (ref "IC11") (pin "10") (pinfunction "SCL_10") (pintype "input"))
      (node (ref "IC11") (pin "16") (pinfunction "VCC_16") (pintype "power_in"))
      (node (ref "IC2") (pin "2") (pinfunction "IN_2") (pintype "input"))
      (node (ref "IC4") (pin "16") (pinfunction "VCC_16") (pintype "power_in"))
      (node (ref "IC4") (pin "6") (pinfunction "G1_6") (pintype "input"))
      (node (ref "IC7") (pin "OUT") (pinfunction "OUT_OUT") (pintype "passive"))
      (node (ref "IC8") (pin "10") (pinfunction "VCC_10") (pintype "power_in"))
      (node (ref "IC8") (pin "30") (pinfunction "AVCC_30") (pintype "power_in"))
      (node (ref "IC9") (pin "16") (pinfunction "VCC_16") (pintype "power_in"))
      (node (ref "JP1") (pin "6") (pinfunction "6_6") (pintype "passive"))
      (node (ref "JP3") (pin "6") (pinfunction "6_6") (pintype "passive"))
      (node (ref "JP5") (pin "6") (pinfunction "6_6") (pintype "passive"))
      (node (ref "JP7") (pin "6") (pinfunction "6_6") (pintype "passive"))
      (node (ref "OK1") (pin "8") (pinfunction "VCC_8") (pintype "passive"))
      (node (ref "R10") (pin "2") (pinfunction "2_2") (pintype "passive"))
      (node (ref "R15") (pin "1") (pinfunction "1_1") (pintype "passive"))
      (node (ref "R16") (pin "2") (pinfunction "2_2") (pintype "passive"))
      (node (ref "R28") (pin "P$1") (pinfunction "E_P$1") (pintype "passive"))
      (node (ref "R29") (pin "P$1") (pinfunction "E_P$1") (pintype "passive"))
      (node (ref "R30") (pin "P$1") (pinfunction "E_P$1") (pintype "passive"))
      (node (ref "R31") (pin "P$1") (pinfunction "E_P$1") (pintype "passive"))
      (node (ref "R36") (pin "1") (pinfunction "E_1") (pintype "passive"))
      (node (ref "R37") (pin "P$1") (pinfunction "E_P$1") (pintype "passive"))
      (node (ref "R38") (pin "P$1") (pinfunction "E_P$1") (pintype "passive"))
      (node (ref "R39") (pin "P$1") (pinfunction "E_P$1") (pintype "passive"))
      (node (ref "R40") (pin "P$1") (pinfunction "E_P$1") (pintype "passive"))
      (node (ref "R9") (pin "2") (pinfunction "2_2") (pintype "passive"))
      (node (ref "RN2") (pin "1") (pinfunction "1_1") (pintype "passive"))
      (node (ref "U$22") (pin "2") (pinfunction "VDD_2") (pintype "power_in"))
      (node (ref "U1") (pin "2") (pinfunction "2_2") (pintype "passive"))
    )
    (net (code "13") (name "AUDIO0") (class "Default")
      (node (ref "JP1") (pin "1") (pinfunction "1_1") (pintype "passive"))
      (node (ref "R2") (pin "1") (pinfunction "1_1") (pintype "passive"))
    )
    (net (code "14") (name "AUDIO1") (class "Default")
      (node (ref "JP1") (pin "2") (pinfunction "2_2") (pintype "passive"))
      (node (ref "R3") (pin "1") (pinfunction "1_1") (pintype "passive"))
    )
    (net (code "15") (name "AUDIO2") (class "Default")
      (node (ref "JP3") (pin "1") (pinfunction "1_1") (pintype "passive"))
      (node (ref "R4") (pin "1") (pinfunction "1_1") (pintype "passive"))
    )
    (net (code "16") (name "AUDIO3") (class "Default")
      (node (ref "JP3") (pin "2") (pinfunction "2_2") (pintype "passive"))
      (node (ref "R5") (pin "1") (pinfunction "1_1") (pintype "passive"))
    )
    (net (code "17") (name "AUDIO4") (class "Default")
      (node (ref "JP5") (pin "1") (pinfunction "1_1") (pintype "passive"))
      (node (ref "R6") (pin "1") (pinfunction "1_1") (pintype "passive"))
    )
    (net (code "18") (name "AUDIO5") (class "Default")
      (node (ref "JP5") (pin "2") (pinfunction "2_2") (pintype "passive"))
      (node (ref "R7") (pin "1") (pinfunction "1_1") (pintype "passive"))
    )
    (net (code "19") (name "ENC_A") (class "Default")
      (node (ref "IC8") (pin "24") (pinfunction "(TCK)PC2_24") (pintype "bidirectional"))
      (node (ref "SW1") (pin "A") (pinfunction "A_A") (pintype "passive"))
    )
    (net (code "20") (name "ENC_B") (class "Default")
      (node (ref "IC8") (pin "25") (pinfunction "(TMS)PC3_25") (pintype "bidirectional"))
      (node (ref "SW1") (pin "B") (pinfunction "B_B") (pintype "passive"))
    )
    (net (code "21") (name "ENC_CLICK") (class "Default")
      (node (ref "IC8") (pin "23") (pinfunction "(SDA)PC1_23") (pintype "bidirectional"))
      (node (ref "SW1") (pin "E") (pinfunction "2_E") (pintype "passive"))
    )
    (net (code "22") (name "GND") (class "Default")
      (node (ref "C1") (pin "2") (pinfunction "2_2") (pintype "passive"))
      (node (ref "C10") (pin "2") (pinfunction "2_2") (pintype "passive"))
      (node (ref "C11") (pin "2") (pinfunction "2_2") (pintype "passive"))
      (node (ref "C12") (pin "-") (pinfunction "-_-") (pintype "passive"))
      (node (ref "C13") (pin "1") (pinfunction "1_1") (pintype "passive"))
      (node (ref "C14") (pin "+") (pinfunction "+_+") (pintype "passive"))
      (node (ref "C15") (pin "2") (pinfunction "2_2") (pintype "passive"))
      (node (ref "C16") (pin "-") (pinfunction "-_-") (pintype "passive"))
      (node (ref "C17") (pin "2") (pinfunction "2_2") (pintype "passive"))
      (node (ref "C18") (pin "2") (pinfunction "2_2") (pintype "passive"))
      (node (ref "C19") (pin "2") (pinfunction "2_2") (pintype "passive"))
      (node (ref "C2") (pin "2") (pinfunction "2_2") (pintype "passive"))
      (node (ref "C20") (pin "2") (pinfunction "2_2") (pintype "passive"))
      (node (ref "C21") (pin "2") (pinfunction "2_2") (pintype "passive"))
      (node (ref "C22") (pin "1") (pinfunction "1_1") (pintype "passive"))
      (node (ref "C23") (pin "-") (pinfunction "-_-") (pintype "passive"))
      (node (ref "C24") (pin "1") (pinfunction "1_1") (pintype "passive"))
      (node (ref "C25") (pin "2") (pinfunction "2_2") (pintype "passive"))
      (node (ref "C26") (pin "2") (pinfunction "2_2") (pintype "passive"))
      (node (ref "C27") (pin "2") (pinfunction "2_2") (pintype "passive"))
      (node (ref "C3") (pin "2") (pinfunction "2_2") (pintype "passive"))
      (node (ref "C4") (pin "+") (pinfunction "+_+") (pintype "passive"))
      (node (ref "C7") (pin "1") (pinfunction "1_1") (pintype "passive"))
      (node (ref "C8") (pin "-") (pinfunction "-_-") (pintype "passive"))
      (node (ref "C9") (pin "-") (pinfunction "-_-") (pintype "passive"))
      (node (ref "D5") (pin "C") (pinfunction "C_C") (pintype "passive"))
      (node (ref "D7") (pin "A") (pinfunction "A_A") (pintype "passive"))
      (node (ref "D9") (pin "A") (pinfunction "A_A") (pintype "passive"))
      (node (ref "IC1") (pin "3") (pinfunction "+IN_3") (pintype "input"))
      (node (ref "IC1") (pin "5") (pinfunction "+IN_5") (pintype "input"))
      (node (ref "IC10") (pin "13") (pinfunction "G_13") (pintype "input"))
      (node (ref "IC10") (pin "8") (pinfunction "GND_8") (pintype "power_in"))
      (node (ref "IC11") (pin "13") (pinfunction "G_13") (pintype "input"))
      (node (ref "IC11") (pin "8") (pinfunction "GND_8") (pintype "power_in"))
      (node (ref "IC2") (pin "1") (pinfunction "GND_1") (pintype "input"))
      (node (ref "IC3") (pin "11") (pinfunction "I_11") (pintype "input"))
      (node (ref "IC3") (pin "14") (pinfunction "I_14") (pintype "input"))
      (node (ref "IC3") (pin "8") (pinfunction "VSS_8") (pintype "power_in"))
      (node (ref "IC3") (pin "9") (pinfunction "I_9") (pintype "input"))
      (node (ref "IC4") (pin "5") (pinfunction "G2B_5") (pintype "input"))
      (node (ref "IC4") (pin "8") (pinfunction "GND_8") (pintype "power_in"))
      (node (ref "IC5") (pin "GND") (pinfunction "GND_GND") (pintype "input"))
      (node (ref "IC6") (pin "GND") (pinfunction "GND_GND") (pintype "input"))
      (node (ref "IC7") (pin "GND") (pinfunction "GND_GND") (pintype "input"))
      (node (ref "IC8") (pin "11") (pinfunction "GND_11") (pintype "power_in"))
      (node (ref "IC8") (pin "31") (pinfunction "GND_31") (pintype "power_in"))
      (node (ref "IC9") (pin "10") (pinfunction "SER_10") (pintype "input"))
      (node (ref "IC9") (pin "15") (pinfunction "INH_15") (pintype "input"))
      (node (ref "IC9") (pin "8") (pinfunction "GND_8") (pintype "power_in"))
      (node (ref "J1") (pin "1") (pinfunction "1_1") (pintype "passive"))
      (node (ref "J2") (pin "S") (pinfunction "S_S") (pintype "passive"))
      (node (ref "J2") (pin "SN") (pinfunction "SN_SN") (pintype "passive"))
      (node (ref "J3") (pin "S") (pinfunction "S_S") (pintype "passive"))
      (node (ref "J3") (pin "SN") (pinfunction "SN_SN") (pintype "passive"))
      (node (ref "J4") (pin "S") (pinfunction "S_S") (pintype "passive"))
      (node (ref "J4") (pin "SN") (pinfunction "SN_SN") (pintype "passive"))
      (node (ref "J5") (pin "S") (pinfunction "S_S") (pintype "passive"))
      (node (ref "J5") (pin "SN") (pinfunction "SN_SN") (pintype "passive"))
      (node (ref "J6") (pin "S") (pinfunction "S_S") (pintype "passive"))
      (node (ref "J6") (pin "SN") (pinfunction "SN_SN") (pintype "passive"))
      (node (ref "J7") (pin "S") (pinfunction "S_S") (pintype "passive"))
      (node (ref "J7") (pin "SN") (pinfunction "SN_SN") (pintype "passive"))
      (node (ref "J8") (pin "S") (pinfunction "S_S") (pintype "passive"))
      (node (ref "J8") (pin "SN") (pinfunction "SN_SN") (pintype "passive"))
      (node (ref "JP1") (pin "4") (pinfunction "4_4") (pintype "passive"))
      (node (ref "JP2") (pin "6") (pinfunction "6_6") (pintype "passive"))
      (node (ref "JP3") (pin "4") (pinfunction "4_4") (pintype "passive"))
      (node (ref "JP4") (pin "6") (pinfunction "6_6") (pintype "passive"))
      (node (ref "JP5") (pin "4") (pinfunction "4_4") (pintype "passive"))
      (node (ref "JP6") (pin "6") (pinfunction "6_6") (pintype "passive"))
      (node (ref "JP7") (pin "5") (pinfunction "5_5") (pintype "passive"))
      (node (ref "OK1") (pin "5") (pinfunction "GND_5") (pintype "passive"))
      (node (ref "R28") (pin "P$3") (pinfunction "A_P$3") (pintype "passive"))
      (node (ref "R29") (pin "P$3") (pinfunction "A_P$3") (pintype "passive"))
      (node (ref "R30") (pin "P$3") (pinfunction "A_P$3") (pintype "passive"))
      (node (ref "R31") (pin "P$3") (pinfunction "A_P$3") (pintype "passive"))
      (node (ref "R36") (pin "3") (pinfunction "A_3") (pintype "passive"))
      (node (ref "R37") (pin "P$3") (pinfunction "A_P$3") (pintype "passive"))
      (node (ref "R38") (pin "P$3") (pinfunction "A_P$3") (pintype "passive"))
      (node (ref "R39") (pin "P$3") (pinfunction "A_P$3") (pintype "passive"))
      (node (ref "R40") (pin "P$3") (pinfunction "A_P$3") (pintype "passive"))
      (node (ref "R41") (pin "P$3") (pinfunction "A_P$3") (pintype "passive"))
      (node (ref "S1") (pin "1") (pinfunction "S_1") (pintype "passive"))
      (node (ref "S1") (pin "2") (pinfunction "S1_2") (pintype "passive"))
      (node (ref "S2") (pin "1") (pinfunction "S_1") (pintype "passive"))
      (node (ref "S2") (pin "2") (pinfunction "S1_2") (pintype "passive"))
      (node (ref "S3") (pin "1") (pinfunction "S_1") (pintype "passive"))
      (node (ref "S3") (pin "2") (pinfunction "S1_2") (pintype "passive"))
      (node (ref "S4") (pin "1") (pinfunction "S_1") (pintype "passive"))
      (node (ref "S4") (pin "2") (pinfunction "S1_2") (pintype "passive"))
      (node (ref "S5") (pin "1") (pinfunction "S_1") (pintype "passive"))
      (node (ref "S5") (pin "2") (pinfunction "S1_2") (pintype "passive"))
      (node (ref "S6") (pin "1") (pinfunction "S_1") (pintype "passive"))
      (node (ref "S6") (pin "2") (pinfunction "S1_2") (pintype "passive"))
      (node (ref "S7") (pin "1") (pinfunction "S_1") (pintype "passive"))
      (node (ref "S7") (pin "2") (pinfunction "S1_2") (pintype "passive"))
      (node (ref "S8") (pin "1") (pinfunction "S_1") (pintype "passive"))
      (node (ref "S8") (pin "2") (pinfunction "S1_2") (pintype "passive"))
      (node (ref "SW1") (pin "C") (pinfunction "C_C") (pintype "passive"))
      (node (ref "SW1") (pin "D") (pinfunction "1_D") (pintype "passive"))
      (node (ref "U$22") (pin "1") (pinfunction "VSS_1") (pintype "power_in"))
      (node (ref "U$22") (pin "16") (pinfunction "K_16") (pintype "power_in"))
      (node (ref "U$22") (pin "5") (pinfunction "R/W_5") (pintype "input"))
      (node (ref "U$26") (pin "3") (pinfunction "VSS1_3") (pintype "power_in"))
      (node (ref "U$26") (pin "6") (pinfunction "VSS2_6") (pintype "power_in"))
      (node (ref "U$26") (pin "GP") (pinfunction "GND_GP") (pintype "power_in"))
      (node (ref "U$26") (pin "GP3") (pinfunction "COMMON_SW_GP3") (pintype "passive"))
      (node (ref "U1") (pin "6") (pinfunction "6_6") (pintype "passive"))
      (node (ref "X2") (pin "2") (pinfunction "2_2") (pintype "passive"))
    )
    (net (code "23") (name "IO_ENABLE") (class "Default")
      (node (ref "IC10") (pin "12") (pinfunction "RCK_12") (pintype "input"))
      (node (ref "IC11") (pin "12") (pinfunction "RCK_12") (pintype "input"))
      (node (ref "IC8") (pin "26") (pinfunction "(TDO)PC4_26") (pintype "bidirectional"))
      (node (ref "IC9") (pin "1") (pinfunction "SH/~{LD}_1") (pintype "input"))
    )
    (net (code "24") (name "IO_INPUT") (class "Default")
      (node (ref "IC8") (pin "28") (pinfunction "(TOSC1)PC6_28") (pintype "bidirectional"))
      (node (ref "IC9") (pin "9") (pinfunction "QH_9") (pintype "output"))
    )
    (net (code "25") (name "IO_OUTPUT") (class "Default")
      (node (ref "IC11") (pin "14") (pinfunction "SER_14") (pintype "input"))
      (node (ref "IC8") (pin "27") (pinfunction "(TDI)PC5_27") (pintype "bidirectional"))
    )
    (net (code "26") (name "IO_SCK") (class "Default")
      (node (ref "IC10") (pin "11") (pinfunction "SCK_11") (pintype "input"))
      (node (ref "IC11") (pin "11") (pinfunction "SCK_11") (pintype "input"))
      (node (ref "IC8") (pin "29") (pinfunction "(TOSC2)PC7_29") (pintype "bidirectional"))
      (node (ref "IC9") (pin "2") (pinfunction "CLK_2") (pintype "input"))
    )
    (net (code "27") (name "LCD_DATA4") (class "Default")
      (node (ref "IC8") (pin "18") (pinfunction "(OC1B)PD4_18") (pintype "bidirectional"))
      (node (ref "U$22") (pin "11") (pinfunction "DB4_11") (pintype "bidirectional"))
    )
    (net (code "28") (name "LCD_DATA5") (class "Default")
      (node (ref "IC8") (pin "19") (pinfunction "(OC1A)PD5_19") (pintype "bidirectional"))
      (node (ref "U$22") (pin "12") (pinfunction "DB5_12") (pintype "bidirectional"))
    )
    (net (code "29") (name "LCD_DATA6") (class "Default")
      (node (ref "IC8") (pin "20") (pinfunction "(ICP)PD6_20") (pintype "bidirectional"))
      (node (ref "U$22") (pin "13") (pinfunction "DB6_13") (pintype "bidirectional"))
    )
    (net (code "30") (name "LCD_DATA7") (class "Default")
      (node (ref "IC8") (pin "21") (pinfunction "(OC2)PD7_21") (pintype "bidirectional"))
      (node (ref "U$22") (pin "14") (pinfunction "DB7_14") (pintype "bidirectional"))
    )
    (net (code "31") (name "LCD_ENABLE") (class "Default")
      (node (ref "IC8") (pin "16") (pinfunction "(INT0)PD2_16") (pintype "bidirectional"))
      (node (ref "U$22") (pin "6") (pinfunction "E_6") (pintype "input"))
    )
    (net (code "32") (name "LCD_RS") (class "Default")
      (node (ref "IC8") (pin "17") (pinfunction "(INT1)PD3_17") (pintype "bidirectional"))
      (node (ref "U$22") (pin "4") (pinfunction "RS_4") (pintype "input"))
    )
    (net (code "33") (name "MIDI_IN") (class "Default")
      (node (ref "IC8") (pin "14") (pinfunction "(RXD)PD0_14") (pintype "bidirectional"))
      (node (ref "OK1") (pin "6") (pinfunction "VO_6") (pintype "passive"))
      (node (ref "R9") (pin "1") (pinfunction "1_1") (pintype "passive"))
    )
    (net (code "34") (name "MIDI_OUT") (class "Default")
      (node (ref "IC8") (pin "15") (pinfunction "(TXD)PD1_15") (pintype "bidirectional"))
      (node (ref "R11") (pin "1") (pinfunction "1_1") (pintype "passive"))
    )
    (net (code "35") (name "MISO") (class "Default")
      (node (ref "IC8") (pin "7") (pinfunction "(MISO)PB6_7") (pintype "bidirectional"))
      (node (ref "JP2") (pin "4") (pinfunction "4_4") (pintype "passive"))
      (node (ref "JP4") (pin "4") (pinfunction "4_4") (pintype "passive"))
      (node (ref "JP6") (pin "4") (pinfunction "4_4") (pintype "passive"))
      (node (ref "JP7") (pin "2") (pinfunction "2_2") (pintype "passive"))
      (node (ref "U$26") (pin "7") (pinfunction "DATA_OUT_7") (pintype "output"))
      (node (ref "U1") (pin "1") (pinfunction "1_1") (pintype "passive"))
    )
    (net (code "36") (name "MOSI") (class "Default")
      (node (ref "IC3") (pin "3") (pinfunction "I_3") (pintype "input"))
      (node (ref "IC8") (pin "6") (pinfunction "(MOSI)PB5_6") (pintype "bidirectional"))
      (node (ref "JP2") (pin "3") (pinfunction "3_3") (pintype "passive"))
      (node (ref "JP4") (pin "3") (pinfunction "3_3") (pintype "passive"))
      (node (ref "JP6") (pin "3") (pinfunction "3_3") (pintype "passive"))
      (node (ref "JP7") (pin "3") (pinfunction "3_3") (pintype "passive"))
      (node (ref "U1") (pin "4") (pinfunction "4_4") (pintype "passive"))
    )
    (net (code "37") (name "Net-(C1-Pad1)") (class "Default")
      (node (ref "C1") (pin "1") (pinfunction "1_1") (pintype "passive"))
      (node (ref "D1") (pin "C") (pinfunction "C_C") (pintype "passive"))
      (node (ref "D2") (pin "A") (pinfunction "A_A") (pintype "passive"))
      (node (ref "SW") (pin "2") (pinfunction "2_2") (pintype "passive"))
    )
    (net (code "38") (name "Net-(C5-Pad2)") (class "Default")
      (node (ref "C5") (pin "2") (pinfunction "2_2") (pintype "passive"))
      (node (ref "J2") (pin "T") (pinfunction "T_T") (pintype "passive"))
      (node (ref "R1") (pin "2") (pinfunction "2_2") (pintype "passive"))
      (node (ref "R12") (pin "2") (pinfunction "2_2") (pintype "passive"))
    )
    (net (code "39") (name "Net-(C12-Pad+)") (class "Default")
      (node (ref "C12") (pin "+") (pinfunction "+_+") (pintype "passive"))
      (node (ref "C15") (pin "1") (pinfunction "1_1") (pintype "passive"))
      (node (ref "C18") (pin "1") (pinfunction "1_1") (pintype "passive"))
      (node (ref "C9") (pin "+") (pinfunction "+_+") (pintype "passive"))
      (node (ref "D2") (pin "C") (pinfunction "C_C") (pintype "passive"))
      (node (ref "D6") (pin "C") (pinfunction "C_C") (pintype "passive"))
      (node (ref "D8") (pin "C") (pinfunction "C_C") (pintype "passive"))
      (node (ref "IC6") (pin "IN") (pinfunction "IN_IN") (pintype "input"))
      (node (ref "IC7") (pin "IN") (pinfunction "IN_IN") (pintype "input"))
    )
    (net (code "40") (name "Net-(C13-Pad2)") (class "Default")
      (node (ref "C13") (pin "2") (pinfunction "2_2") (pintype "passive"))
      (node (ref "C4") (pin "-") (pinfunction "-_-") (pintype "passive"))
      (node (ref "D1") (pin "A") (pinfunction "A_A") (pintype "passive"))
      (node (ref "D4") (pin "A") (pinfunction "A_A") (pintype "passive"))
      (node (ref "IC5") (pin "IN") (pinfunction "IN_IN") (pintype "input"))
    )
    (net (code "41") (name "Net-(IC1A--IN)") (class "Default")
      (node (ref "C5") (pin "1") (pinfunction "1_1") (pintype "passive"))
      (node (ref "IC1") (pin "2") (pinfunction "-IN_2") (pintype "input"))
      (node (ref "R12") (pin "1") (pinfunction "1_1") (pintype "passive"))
      (node (ref "R14") (pin "2") (pinfunction "2_2") (pintype "passive"))
    )
    (net (code "42") (name "Net-(IC1A-OUT)") (class "Default")
      (node (ref "IC1") (pin "1") (pinfunction "OUT_1") (pintype "output"))
      (node (ref "R1") (pin "1") (pinfunction "1_1") (pintype "passive"))
    )
    (net (code "43") (name "Net-(IC1B--IN)") (class "Default")
      (node (ref "C6") (pin "1") (pinfunction "1_1") (pintype "passive"))
      (node (ref "IC1") (pin "6") (pinfunction "-IN_6") (pintype "input"))
      (node (ref "R13") (pin "1") (pinfunction "1_1") (pintype "passive"))
      (node (ref "RN1") (pin "1") (pinfunction "1_1") (pintype "passive"))
    )
    (net (code "44") (name "Net-(IC1B-OUT)") (class "Default")
      (node (ref "C6") (pin "2") (pinfunction "2_2") (pintype "passive"))
      (node (ref "IC1") (pin "7") (pinfunction "OUT_7") (pintype "output"))
      (node (ref "R13") (pin "2") (pinfunction "2_2") (pintype "passive"))
      (node (ref "R41") (pin "P$1") (pinfunction "E_P$1") (pintype "passive"))
    )
    (net (code "45") (name "Net-(IC3A-O)") (class "Default")
      (node (ref "IC3") (pin "2") (pinfunction "O_2") (pintype "output"))
      (node (ref "U$26") (pin "2") (pinfunction "DATA_IN_2") (pintype "input"))
    )
    (net (code "46") (name "Net-(IC3B-O)") (class "Default")
      (node (ref "IC3") (pin "4") (pinfunction "O_4") (pintype "output"))
      (node (ref "U$26") (pin "5") (pinfunction "SCLK_5") (pintype "input"))
    )
    (net (code "47") (name "Net-(IC3C-O)") (class "Default")
      (node (ref "IC3") (pin "6") (pinfunction "O_6") (pintype "output"))
      (node (ref "U$26") (pin "1") (pinfunction "CS_1") (pintype "input"))
    )
    (net (code "48") (name "Net-(IC8-AREF)") (class "Default")
      (node (ref "C19") (pin "1") (pinfunction "1_1") (pintype "passive"))
      (node (ref "IC8") (pin "32") (pinfunction "AREF_32") (pintype "passive"))
    )
    (net (code "49") (name "Net-(IC8-XTAL1)") (class "Default")
      (node (ref "C24") (pin "2") (pinfunction "2_2") (pintype "passive"))
      (node (ref "IC8") (pin "13") (pinfunction "XTAL1_13") (pintype "bidirectional"))
      (node (ref "Q1") (pin "1") (pinfunction "1_1") (pintype "passive"))
    )
    (net (code "50") (name "Net-(IC8-XTAL2)") (class "Default")
      (node (ref "C22") (pin "2") (pinfunction "2_2") (pintype "passive"))
      (node (ref "IC8") (pin "12") (pinfunction "XTAL2_12") (pintype "bidirectional"))
      (node (ref "Q1") (pin "2") (pinfunction "2_2") (pintype "passive"))
    )
    (net (code "51") (name "Net-(IC9A-A)") (class "Default")
      (node (ref "IC9") (pin "11") (pinfunction "A_11") (pintype "input"))
      (node (ref "RN2") (pin "9") (pinfunction "9_9") (pintype "passive"))
      (node (ref "S1") (pin "3") (pinfunction "P_3") (pintype "passive"))
      (node (ref "S1") (pin "4") (pinfunction "P1_4") (pintype "passive"))
    )
    (net (code "52") (name "Net-(IC9A-B)") (class "Default")
      (node (ref "IC9") (pin "12") (pinfunction "B_12") (pintype "input"))
      (node (ref "RN2") (pin "8") (pinfunction "8_8") (pintype "passive"))
      (node (ref "S2") (pin "3") (pinfunction "P_3") (pintype "passive"))
      (node (ref "S2") (pin "4") (pinfunction "P1_4") (pintype "passive"))
    )
    (net (code "53") (name "Net-(IC9A-C)") (class "Default")
      (node (ref "IC9") (pin "13") (pinfunction "C_13") (pintype "input"))
      (node (ref "RN2") (pin "7") (pinfunction "7_7") (pintype "passive"))
      (node (ref "S3") (pin "3") (pinfunction "P_3") (pintype "passive"))
      (node (ref "S3") (pin "4") (pinfunction "P1_4") (pintype "passive"))
    )
    (net (code "54") (name "Net-(IC9A-D)") (class "Default")
      (node (ref "IC9") (pin "14") (pinfunction "D_14") (pintype "input"))
      (node (ref "RN2") (pin "6") (pinfunction "6_6") (pintype "passive"))
      (node (ref "S4") (pin "3") (pinfunction "P_3") (pintype "passive"))
      (node (ref "S4") (pin "4") (pinfunction "P1_4") (pintype "passive"))
    )
    (net (code "55") (name "Net-(IC9A-E)") (class "Default")
      (node (ref "IC9") (pin "3") (pinfunction "E_3") (pintype "input"))
      (node (ref "RN2") (pin "5") (pinfunction "5_5") (pintype "passive"))
      (node (ref "S5") (pin "3") (pinfunction "P_3") (pintype "passive"))
      (node (ref "S5") (pin "4") (pinfunction "P1_4") (pintype "passive"))
    )
    (net (code "56") (name "Net-(IC9A-F)") (class "Default")
      (node (ref "IC9") (pin "4") (pinfunction "F_4") (pintype "input"))
      (node (ref "RN2") (pin "4") (pinfunction "4_4") (pintype "passive"))
      (node (ref "S6") (pin "3") (pinfunction "P_3") (pintype "passive"))
      (node (ref "S6") (pin "4") (pinfunction "P1_4") (pintype "passive"))
    )
    (net (code "57") (name "Net-(IC9A-G)") (class "Default")
      (node (ref "IC9") (pin "5") (pinfunction "G_5") (pintype "input"))
      (node (ref "RN2") (pin "3") (pinfunction "3_3") (pintype "passive"))
      (node (ref "S7") (pin "3") (pinfunction "P_3") (pintype "passive"))
      (node (ref "S7") (pin "4") (pinfunction "P1_4") (pintype "passive"))
    )
    (net (code "58") (name "Net-(IC9A-H)") (class "Default")
      (node (ref "IC9") (pin "6") (pinfunction "H_6") (pintype "input"))
      (node (ref "RN2") (pin "2") (pinfunction "2_2") (pintype "passive"))
      (node (ref "S8") (pin "3") (pinfunction "P_3") (pintype "passive"))
      (node (ref "S8") (pin "4") (pinfunction "P1_4") (pintype "passive"))
    )
    (net (code "59") (name "Net-(IC10A-QA)") (class "Default")
      (node (ref "IC10") (pin "15") (pinfunction "QA_15") (pintype "tri_state"))
      (node (ref "R34") (pin "1") (pinfunction "1_1") (pintype "passive"))
    )
    (net (code "60") (name "Net-(IC10A-QB)") (class "Default")
      (node (ref "IC10") (pin "1") (pinfunction "QB_1") (pintype "tri_state"))
      (node (ref "R32") (pin "1") (pinfunction "1_1") (pintype "passive"))
    )
    (net (code "61") (name "Net-(IC10A-QC)") (class "Default")
      (node (ref "IC10") (pin "2") (pinfunction "QC_2") (pintype "tri_state"))
      (node (ref "R26") (pin "1") (pinfunction "1_1") (pintype "passive"))
    )
    (net (code "62") (name "Net-(IC10A-QD)") (class "Default")
      (node (ref "IC10") (pin "3") (pinfunction "QD_3") (pintype "tri_state"))
      (node (ref "R24") (pin "1") (pinfunction "1_1") (pintype "passive"))
    )
    (net (code "63") (name "Net-(IC10A-QE)") (class "Default")
      (node (ref "IC10") (pin "4") (pinfunction "QE_4") (pintype "tri_state"))
      (node (ref "R22") (pin "1") (pinfunction "1_1") (pintype "passive"))
    )
    (net (code "64") (name "Net-(IC10A-QF)") (class "Default")
      (node (ref "IC10") (pin "5") (pinfunction "QF_5") (pintype "tri_state"))
      (node (ref "R20") (pin "1") (pinfunction "1_1") (pintype "passive"))
    )
    (net (code "65") (name "Net-(IC10A-QG)") (class "Default")
      (node (ref "IC10") (pin "6") (pinfunction "QG_6") (pintype "tri_state"))
      (node (ref "R18") (pin "1") (pinfunction "1_1") (pintype "passive"))
    )
    (net (code "66") (name "Net-(IC10A-QH)") (class "Default")
      (node (ref "IC10") (pin "7") (pinfunction "QH_7") (pintype "tri_state"))
      (node (ref "LED1") (pin "K") (pinfunction "C_K") (pintype "passive"))
      (node (ref "LED10") (pin "K") (pinfunction "C_K") (pintype "passive"))
      (node (ref "LED11") (pin "K") (pinfunction "C_K") (pintype "passive"))
      (node (ref "LED12") (pin "K") (pinfunction "C_K") (pintype "passive"))
      (node (ref "LED13") (pin "K") (pinfunction "C_K") (pintype "passive"))
      (node (ref "LED14") (pin "K") (pinfunction "C_K") (pintype "passive"))
      (node (ref "LED15") (pin "K") (pinfunction "C_K") (pintype "passive"))
      (node (ref "LED2") (pin "K") (pinfunction "C_K") (pintype "passive"))
      (node (ref "LED3") (pin "K") (pinfunction "C_K") (pintype "passive"))
      (node (ref "LED4") (pin "K") (pinfunction "C_K") (pintype "passive"))
      (node (ref "LED5") (pin "K") (pinfunction "C_K") (pintype "passive"))
      (node (ref "LED6") (pin "K") (pinfunction "C_K") (pintype "passive"))
      (node (ref "LED7") (pin "K") (pinfunction "C_K") (pintype "passive"))
      (node (ref "LED8") (pin "K") (pinfunction "C_K") (pintype "passive"))
      (node (ref "LED9") (pin "K") (pinfunction "C_K") (pintype "passive"))
    )
    (net (code "67") (name "Net-(IC10A-SER)") (class "Default")
      (node (ref "IC10") (pin "14") (pinfunction "SER_14") (pintype "input"))
      (node (ref "IC11") (pin "9") (pinfunction "QH*_9") (pintype "tri_state"))
    )
    (net (code "68") (name "Net-(IC11A-QA)") (class "Default")
      (node (ref "IC11") (pin "15") (pinfunction "QA_15") (pintype "tri_state"))
      (node (ref "R35") (pin "1") (pinfunction "1_1") (pintype "passive"))
    )
    (net (code "69") (name "Net-(IC11A-QB)") (class "Default")
      (node (ref "IC11") (pin "1") (pinfunction "QB_1") (pintype "tri_state"))
      (node (ref "R33") (pin "1") (pinfunction "1_1") (pintype "passive"))
    )
    (net (code "70") (name "Net-(IC11A-QC)") (class "Default")
      (node (ref "IC11") (pin "2") (pinfunction "QC_2") (pintype "tri_state"))
      (node (ref "R27") (pin "1") (pinfunction "1_1") (pintype "passive"))
    )
    (net (code "71") (name "Net-(IC11A-QD)") (class "Default")
      (node (ref "IC11") (pin "3") (pinfunction "QD_3") (pintype "tri_state"))
      (node (ref "R25") (pin "1") (pinfunction "1_1") (pintype "passive"))
    )
    (net (code "72") (name "Net-(IC11A-QE)") (class "Default")
      (node (ref "IC11") (pin "4") (pinfunction "QE_4") (pintype "tri_state"))
      (node (ref "R23") (pin "1") (pinfunction "1_1") (pintype "passive"))
    )
    (net (code "73") (name "Net-(IC11A-QF)") (class "Default")
      (node (ref "IC11") (pin "5") (pinfunction "QF_5") (pintype "tri_state"))
      (node (ref "R21") (pin "1") (pinfunction "1_1") (pintype "passive"))
    )
    (net (code "74") (name "Net-(IC11A-QG)") (class "Default")
      (node (ref "IC11") (pin "6") (pinfunction "QG_6") (pintype "tri_state"))
      (node (ref "R19") (pin "1") (pinfunction "1_1") (pintype "passive"))
    )
    (net (code "75") (name "Net-(IC11A-QH)") (class "Default")
      (node (ref "IC11") (pin "7") (pinfunction "QH_7") (pintype "tri_state"))
      (node (ref "R17") (pin "1") (pinfunction "1_1") (pintype "passive"))
    )
    (net (code "76") (name "Net-(J1-Pad3)") (class "Default")
      (node (ref "J1") (pin "3") (pinfunction "3_3") (pintype "passive"))
      (node (ref "SW") (pin "1") (pinfunction "1_1") (pintype "passive"))
    )
    (net (code "77") (name "Net-(J3-PadT)") (class "Default")
      (node (ref "J3") (pin "T") (pinfunction "T_T") (pintype "passive"))
      (node (ref "R2") (pin "2") (pinfunction "2_2") (pintype "passive"))
    )
    (net (code "78") (name "Net-(J4-PadT)") (class "Default")
      (node (ref "J4") (pin "T") (pinfunction "T_T") (pintype "passive"))
      (node (ref "R3") (pin "2") (pinfunction "2_2") (pintype "passive"))
    )
    (net (code "79") (name "Net-(J5-PadT)") (class "Default")
      (node (ref "J5") (pin "T") (pinfunction "T_T") (pintype "passive"))
      (node (ref "R4") (pin "2") (pinfunction "2_2") (pintype "passive"))
    )
    (net (code "80") (name "Net-(J6-PadT)") (class "Default")
      (node (ref "J6") (pin "T") (pinfunction "T_T") (pintype "passive"))
      (node (ref "R5") (pin "2") (pinfunction "2_2") (pintype "passive"))
    )
    (net (code "81") (name "Net-(J7-PadT)") (class "Default")
      (node (ref "J7") (pin "T") (pinfunction "T_T") (pintype "passive"))
      (node (ref "R6") (pin "2") (pinfunction "2_2") (pintype "passive"))
    )
    (net (code "82") (name "Net-(J8-PadT)") (class "Default")
      (node (ref "J8") (pin "T") (pinfunction "T_T") (pintype "passive"))
      (node (ref "R7") (pin "2") (pinfunction "2_2") (pintype "passive"))
    )
    (net (code "83") (name "Net-(LED1-PadA)") (class "Default")
      (node (ref "LED1") (pin "A") (pinfunction "A_A") (pintype "passive"))
      (node (ref "R26") (pin "2") (pinfunction "2_2") (pintype "passive"))
    )
    (net (code "84") (name "Net-(LED2-PadA)") (class "Default")
      (node (ref "LED2") (pin "A") (pinfunction "A_A") (pintype "passive"))
      (node (ref "R20") (pin "2") (pinfunction "2_2") (pintype "passive"))
    )
    (net (code "85") (name "Net-(LED3-PadA)") (class "Default")
      (node (ref "LED3") (pin "A") (pinfunction "A_A") (pintype "passive"))
      (node (ref "R32") (pin "2") (pinfunction "2_2") (pintype "passive"))
    )
    (net (code "86") (name "Net-(LED4-PadA)") (class "Default")
      (node (ref "LED4") (pin "A") (pinfunction "A_A") (pintype "passive"))
      (node (ref "R22") (pin "2") (pinfunction "2_2") (pintype "passive"))
    )
    (net (code "87") (name "Net-(LED5-PadA)") (class "Default")
      (node (ref "LED5") (pin "A") (pinfunction "A_A") (pintype "passive"))
      (node (ref "R34") (pin "2") (pinfunction "2_2") (pintype "passive"))
    )
    (net (code "88") (name "Net-(LED6-PadA)") (class "Default")
      (node (ref "LED6") (pin "A") (pinfunction "A_A") (pintype "passive"))
      (node (ref "R24") (pin "2") (pinfunction "2_2") (pintype "passive"))
    )
    (net (code "89") (name "Net-(LED7-PadA)") (class "Default")
      (node (ref "LED7") (pin "A") (pinfunction "A_A") (pintype "passive"))
      (node (ref "R18") (pin "2") (pinfunction "2_2") (pintype "passive"))
    )
    (net (code "90") (name "Net-(LED8-PadA)") (class "Default")
      (node (ref "LED8") (pin "A") (pinfunction "A_A") (pintype "passive"))
      (node (ref "R35") (pin "2") (pinfunction "2_2") (pintype "passive"))
    )
    (net (code "91") (name "Net-(LED9-PadA)") (class "Default")
      (node (ref "LED9") (pin "A") (pinfunction "A_A") (pintype "passive"))
      (node (ref "R33") (pin "2") (pinfunction "2_2") (pintype "passive"))
    )
    (net (code "92") (name "Net-(LED10-PadA)") (class "Default")
      (node (ref "LED10") (pin "A") (pinfunction "A_A") (pintype "passive"))
      (node (ref "R27") (pin "2") (pinfunction "2_2") (pintype "passive"))
    )
    (net (code "93") (name "Net-(LED11-PadA)") (class "Default")
      (node (ref "LED11") (pin "A") (pinfunction "A_A") (pintype "passive"))
      (node (ref "R25") (pin "2") (pinfunction "2_2") (pintype "passive"))
    )
    (net (code "94") (name "Net-(LED12-PadA)") (class "Default")
      (node (ref "LED12") (pin "A") (pinfunction "A_A") (pintype "passive"))
      (node (ref "R23") (pin "2") (pinfunction "2_2") (pintype "passive"))
    )
    (net (code "95") (name "Net-(LED13-PadA)") (class "Default")
      (node (ref "LED13") (pin "A") (pinfunction "A_A") (pintype "passive"))
      (node (ref "R21") (pin "2") (pinfunction "2_2") (pintype "passive"))
    )
    (net (code "96") (name "Net-(LED14-PadA)") (class "Default")
      (node (ref "LED14") (pin "A") (pinfunction "A_A") (pintype "passive"))
      (node (ref "R19") (pin "2") (pinfunction "2_2") (pintype "passive"))
    )
    (net (code "97") (name "Net-(LED15-PadA)") (class "Default")
      (node (ref "LED15") (pin "A") (pinfunction "A_A") (pintype "passive"))
      (node (ref "R17") (pin "2") (pinfunction "2_2") (pintype "passive"))
    )
    (net (code "98") (name "Net-(OK1-A)") (class "Default")
      (node (ref "D3") (pin "C") (pinfunction "C_C") (pintype "passive"))
      (node (ref "OK1") (pin "2") (pinfunction "A_2") (pintype "passive"))
      (node (ref "R8") (pin "2") (pinfunction "2_2") (pintype "passive"))
    )
    (net (code "99") (name "Net-(OK1-C)") (class "Default")
      (node (ref "D3") (pin "A") (pinfunction "A_A") (pintype "passive"))
      (node (ref "OK1") (pin "3") (pinfunction "C_3") (pintype "passive"))
      (node (ref "X1") (pin "5") (pinfunction "5_5") (pintype "passive"))
    )
    (net (code "100") (name "Net-(R8-Pad1)") (class "Default")
      (node (ref "R8") (pin "1") (pinfunction "1_1") (pintype "passive"))
      (node (ref "X1") (pin "4") (pinfunction "4_4") (pintype "passive"))
    )
    (net (code "101") (name "Net-(R10-Pad1)") (class "Default")
      (node (ref "R10") (pin "1") (pinfunction "1_1") (pintype "passive"))
      (node (ref "X2") (pin "4") (pinfunction "4_4") (pintype "passive"))
    )
    (net (code "102") (name "Net-(R11-Pad2)") (class "Default")
      (node (ref "R11") (pin "2") (pinfunction "2_2") (pintype "passive"))
      (node (ref "X2") (pin "5") (pinfunction "5_5") (pintype "passive"))
    )
    (net (code "103") (name "Net-(R36-S)") (class "Default")
      (node (ref "R36") (pin "2") (pinfunction "S_2") (pintype "passive"))
      (node (ref "U$22") (pin "3") (pinfunction "VO_3") (pintype "bidirectional"))
    )
    (net (code "104") (name "Net-(R41-S)") (class "Default")
      (node (ref "R14") (pin "1") (pinfunction "1_1") (pintype "passive"))
      (node (ref "R41") (pin "P$2") (pinfunction "S_P$2") (pintype "passive"))
    )
    (net (code "105") (name "Net-(U$22-A)") (class "Default")
      (node (ref "R15") (pin "2") (pinfunction "2_2") (pintype "passive"))
      (node (ref "U$22") (pin "15") (pinfunction "A_15") (pintype "power_in"))
    )
    (net (code "106") (name "POTS0") (class "Default")
      (node (ref "IC8") (pin "40") (pinfunction "(ADC0)PA0_40") (pintype "bidirectional"))
      (node (ref "R40") (pin "P$2") (pinfunction "S_P$2") (pintype "passive"))
    )
    (net (code "107") (name "POTS1") (class "Default")
      (node (ref "IC8") (pin "39") (pinfunction "(ADC1)PA1_39") (pintype "bidirectional"))
      (node (ref "R39") (pin "P$2") (pinfunction "S_P$2") (pintype "passive"))
    )
    (net (code "108") (name "POTS2") (class "Default")
      (node (ref "IC8") (pin "38") (pinfunction "(ADC2)PA2_38") (pintype "bidirectional"))
      (node (ref "R38") (pin "P$2") (pinfunction "S_P$2") (pintype "passive"))
    )
    (net (code "109") (name "POTS3") (class "Default")
      (node (ref "IC8") (pin "37") (pinfunction "(ADC3)PA3_37") (pintype "bidirectional"))
      (node (ref "R37") (pin "P$2") (pinfunction "S_P$2") (pintype "passive"))
    )
    (net (code "110") (name "POTS4") (class "Default")
      (node (ref "IC8") (pin "36") (pinfunction "(ADC4)PA4_36") (pintype "bidirectional"))
      (node (ref "R28") (pin "P$2") (pinfunction "S_P$2") (pintype "passive"))
    )
    (net (code "111") (name "POTS5") (class "Default")
      (node (ref "IC8") (pin "35") (pinfunction "(ADC5)PA5_35") (pintype "bidirectional"))
      (node (ref "R29") (pin "P$2") (pinfunction "S_P$2") (pintype "passive"))
    )
    (net (code "112") (name "POTS6") (class "Default")
      (node (ref "IC8") (pin "34") (pinfunction "(ADC6)PA6_34") (pintype "bidirectional"))
      (node (ref "R30") (pin "P$2") (pinfunction "S_P$2") (pintype "passive"))
    )
    (net (code "113") (name "POTS7") (class "Default")
      (node (ref "IC8") (pin "33") (pinfunction "(ADC7)PA7_33") (pintype "bidirectional"))
      (node (ref "R31") (pin "P$2") (pinfunction "S_P$2") (pintype "passive"))
    )
    (net (code "114") (name "RESET") (class "Default")
      (node (ref "C17") (pin "1") (pinfunction "1_1") (pintype "passive"))
      (node (ref "IC8") (pin "9") (pinfunction "RESET_9") (pintype "input"))
      (node (ref "R16") (pin "1") (pinfunction "1_1") (pintype "passive"))
      (node (ref "U1") (pin "5") (pinfunction "5_5") (pintype "passive"))
    )
    (net (code "115") (name "RS0") (class "Default")
      (node (ref "J3") (pin "TN") (pinfunction "TN_TN") (pintype "passive"))
      (node (ref "RN1") (pin "2") (pinfunction "2_2") (pintype "passive"))
    )
    (net (code "116") (name "RS1") (class "Default")
      (node (ref "J4") (pin "TN") (pinfunction "TN_TN") (pintype "passive"))
      (node (ref "RN1") (pin "3") (pinfunction "3_3") (pintype "passive"))
    )
    (net (code "117") (name "RS2") (class "Default")
      (node (ref "J5") (pin "TN") (pinfunction "TN_TN") (pintype "passive"))
      (node (ref "RN1") (pin "4") (pinfunction "4_4") (pintype "passive"))
    )
    (net (code "118") (name "RS3") (class "Default")
      (node (ref "J6") (pin "TN") (pinfunction "TN_TN") (pintype "passive"))
      (node (ref "RN1") (pin "5") (pinfunction "5_5") (pintype "passive"))
    )
    (net (code "119") (name "RS4") (class "Default")
      (node (ref "J7") (pin "TN") (pinfunction "TN_TN") (pintype "passive"))
      (node (ref "RN1") (pin "6") (pinfunction "6_6") (pintype "passive"))
    )
    (net (code "120") (name "RS5") (class "Default")
      (node (ref "J8") (pin "TN") (pinfunction "TN_TN") (pintype "passive"))
      (node (ref "RN1") (pin "7") (pinfunction "7_7") (pintype "passive"))
    )
    (net (code "121") (name "SCK") (class "Default")
      (node (ref "IC3") (pin "5") (pinfunction "I_5") (pintype "input"))
      (node (ref "IC8") (pin "8") (pinfunction "(SCK)PB7_8") (pintype "bidirectional"))
      (node (ref "JP2") (pin "5") (pinfunction "5_5") (pintype "passive"))
      (node (ref "JP4") (pin "5") (pinfunction "5_5") (pintype "passive"))
      (node (ref "JP6") (pin "5") (pinfunction "5_5") (pintype "passive"))
      (node (ref "JP7") (pin "1") (pinfunction "1_1") (pintype "passive"))
      (node (ref "U1") (pin "3") (pinfunction "3_3") (pintype "passive"))
    )
    (net (code "122") (name "SS") (class "Default")
      (node (ref "IC4") (pin "4") (pinfunction "G2A_4") (pintype "input"))
      (node (ref "IC8") (pin "5") (pinfunction "(SS)PB4_5") (pintype "bidirectional"))
    )
    (net (code "123") (name "SS0") (class "Default")
      (node (ref "IC4") (pin "15") (pinfunction "Y0_15") (pintype "output"))
      (node (ref "JP2") (pin "1") (pinfunction "1_1") (pintype "passive"))
    )
    (net (code "124") (name "SS1") (class "Default")
      (node (ref "IC4") (pin "14") (pinfunction "Y1_14") (pintype "output"))
      (node (ref "JP2") (pin "2") (pinfunction "2_2") (pintype "passive"))
    )
    (net (code "125") (name "SS2") (class "Default")
      (node (ref "IC4") (pin "13") (pinfunction "Y2_13") (pintype "output"))
      (node (ref "JP4") (pin "1") (pinfunction "1_1") (pintype "passive"))
    )
    (net (code "126") (name "SS3") (class "Default")
      (node (ref "IC4") (pin "12") (pinfunction "Y3_12") (pintype "output"))
      (node (ref "JP4") (pin "2") (pinfunction "2_2") (pintype "passive"))
    )
    (net (code "127") (name "SS4") (class "Default")
      (node (ref "IC4") (pin "11") (pinfunction "Y4_11") (pintype "output"))
      (node (ref "JP6") (pin "1") (pinfunction "1_1") (pintype "passive"))
    )
    (net (code "128") (name "SS5") (class "Default")
      (node (ref "IC4") (pin "10") (pinfunction "Y5_10") (pintype "output"))
      (node (ref "JP6") (pin "2") (pinfunction "2_2") (pintype "passive"))
    )
    (net (code "129") (name "SS6") (class "Default")
      (node (ref "IC4") (pin "9") (pinfunction "Y6_9") (pintype "output"))
      (node (ref "JP7") (pin "4") (pinfunction "4_4") (pintype "passive"))
    )
    (net (code "130") (name "SS7") (class "Default")
      (node (ref "IC3") (pin "7") (pinfunction "I_7") (pintype "input"))
      (node (ref "IC4") (pin "7") (pinfunction "Y7_7") (pintype "output"))
    )
    (net (code "131") (name "SS_ADDR0") (class "Default")
      (node (ref "IC4") (pin "1") (pinfunction "A_1") (pintype "input"))
      (node (ref "IC8") (pin "1") (pinfunction "(T0/XCK)PB0_1") (pintype "bidirectional"))
    )
    (net (code "132") (name "SS_ADDR1") (class "Default")
      (node (ref "IC4") (pin "2") (pinfunction "B_2") (pintype "input"))
      (node (ref "IC8") (pin "2") (pinfunction "(T1)PB1_2") (pintype "bidirectional"))
    )
    (net (code "133") (name "SS_ADDR2") (class "Default")
      (node (ref "IC4") (pin "3") (pinfunction "C_3") (pintype "input"))
      (node (ref "IC8") (pin "3") (pinfunction "(AIN0/INT2)PB2_3") (pintype "bidirectional"))
    )
    (net (code "134") (name "VCC") (class "Default")
      (node (ref "C16") (pin "+") (pinfunction "+_+") (pintype "passive"))
      (node (ref "C3") (pin "1") (pinfunction "1_1") (pintype "passive"))
      (node (ref "D6") (pin "A") (pinfunction "A_A") (pintype "passive"))
      (node (ref "D7") (pin "C") (pinfunction "C_C") (pintype "passive"))
      (node (ref "IC1") (pin "8") (pinfunction "V+_8") (pintype "power_in"))
      (node (ref "IC6") (pin "OUT") (pinfunction "OUT_OUT") (pintype "passive"))
      (node (ref "JP1") (pin "3") (pinfunction "3_3") (pintype "passive"))
      (node (ref "JP3") (pin "3") (pinfunction "3_3") (pintype "passive"))
      (node (ref "JP5") (pin "3") (pinfunction "3_3") (pintype "passive"))
    )
    (net (code "135") (name "VEE") (class "Default")
      (node (ref "C14") (pin "-") (pinfunction "-_-") (pintype "passive"))
      (node (ref "C7") (pin "2") (pinfunction "2_2") (pintype "passive"))
      (node (ref "D4") (pin "C") (pinfunction "C_C") (pintype "passive"))
      (node (ref "D5") (pin "A") (pinfunction "A_A") (pintype "passive"))
      (node (ref "IC1") (pin "4") (pinfunction "V-_4") (pintype "power_in"))
      (node (ref "IC5") (pin "OUT") (pinfunction "OUT_OUT") (pintype "passive"))
      (node (ref "JP1") (pin "5") (pinfunction "5_5") (pintype "passive"))
      (node (ref "JP3") (pin "5") (pinfunction "5_5") (pintype "passive"))
      (node (ref "JP5") (pin "5") (pinfunction "5_5") (pintype "passive"))
    )
    (net (code "136") (name "unconnected-(IC3D-O-Pad10)") (class "Default")
      (node (ref "IC3") (pin "10") (pinfunction "O_10") (pintype "output"))
    )
    (net (code "137") (name "unconnected-(IC3E-O-Pad12)") (class "Default")
      (node (ref "IC3") (pin "12") (pinfunction "O_12") (pintype "output"))
    )
    (net (code "138") (name "unconnected-(IC3F-O-Pad15)") (class "Default")
      (node (ref "IC3") (pin "15") (pinfunction "O_15") (pintype "output"))
    )
    (net (code "139") (name "unconnected-(IC8-(AIN1{slash}OC0)PB3-Pad4)") (class "Default")
      (node (ref "IC8") (pin "4") (pinfunction "(AIN1/OC0)PB3_4") (pintype "bidirectional"))
    )
    (net (code "140") (name "unconnected-(IC8-(SCL)PC0-Pad22)") (class "Default")
      (node (ref "IC8") (pin "22") (pinfunction "(SCL)PC0_22") (pintype "bidirectional"))
    )
    (net (code "141") (name "unconnected-(IC9A-~{QH}-Pad7)") (class "Default")
      (node (ref "IC9") (pin "7") (pinfunction "~{QH}_7") (pintype "output"))
    )
    (net (code "142") (name "unconnected-(IC10A-QH*-Pad9)") (class "Default")
      (node (ref "IC10") (pin "9") (pinfunction "QH*_9") (pintype "tri_state"))
    )
    (net (code "143") (name "unconnected-(J1-Pad2)") (class "Default")
      (node (ref "J1") (pin "2") (pinfunction "2_2") (pintype "passive"))
    )
    (net (code "144") (name "unconnected-(J2-PadTN)") (class "Default")
      (node (ref "J2") (pin "TN") (pinfunction "TN_TN") (pintype "passive"))
    )
    (net (code "145") (name "unconnected-(OK1-VB-Pad7)") (class "Default")
      (node (ref "OK1") (pin "7") (pinfunction "VB_7") (pintype "passive"))
    )
    (net (code "146") (name "unconnected-(U$22-DB0-Pad7)") (class "Default")
      (node (ref "U$22") (pin "7") (pinfunction "DB0_7") (pintype "bidirectional"))
    )
    (net (code "147") (name "unconnected-(U$22-DB1-Pad8)") (class "Default")
      (node (ref "U$22") (pin "8") (pinfunction "DB1_8") (pintype "bidirectional"))
    )
    (net (code "148") (name "unconnected-(U$22-DB2-Pad9)") (class "Default")
      (node (ref "U$22") (pin "9") (pinfunction "DB2_9") (pintype "bidirectional"))
    )
    (net (code "149") (name "unconnected-(U$22-DB3-Pad10)") (class "Default")
      (node (ref "U$22") (pin "10") (pinfunction "DB3_10") (pintype "bidirectional"))
    )
    (net (code "150") (name "unconnected-(U$26-CARD_DETECT-PadCD)") (class "Default")
      (node (ref "U$26") (pin "CD") (pinfunction "CARD_DETECT_CD") (pintype "passive"))
    )
    (net (code "151") (name "unconnected-(U$26-DAT1-Pad8)") (class "Default")
      (node (ref "U$26") (pin "8") (pinfunction "DAT1_8") (pintype "bidirectional"))
    )
    (net (code "152") (name "unconnected-(U$26-DAT2-Pad9)") (class "Default")
      (node (ref "U$26") (pin "9") (pinfunction "DAT2_9") (pintype "bidirectional"))
    )
    (net (code "153") (name "unconnected-(U$26-WRITE_PROTECT-PadWP)") (class "Default")
      (node (ref "U$26") (pin "WP") (pinfunction "WRITE_PROTECT_WP") (pintype "passive"))
    )
    (net (code "154") (name "unconnected-(X1-Pad1)") (class "Default")
      (node (ref "X1") (pin "1") (pinfunction "1_1") (pintype "passive"))
    )
    (net (code "155") (name "unconnected-(X1-Pad2)") (class "Default")
      (node (ref "X1") (pin "2") (pinfunction "2_2") (pintype "passive"))
    )
    (net (code "156") (name "unconnected-(X1-Pad3)") (class "Default")
      (node (ref "X1") (pin "3") (pinfunction "3_3") (pintype "passive"))
    )
    (net (code "157") (name "unconnected-(X2-Pad1)") (class "Default")
      (node (ref "X2") (pin "1") (pinfunction "1_1") (pintype "passive"))
    )
    (net (code "158") (name "unconnected-(X2-Pad3)") (class "Default")
      (node (ref "X2") (pin "3") (pinfunction "3_3") (pintype "passive"))
    )
  )
)
